# EMG_SS19_Version_2_0.net
KiCad netlist of a schematic drawn in EAGLE
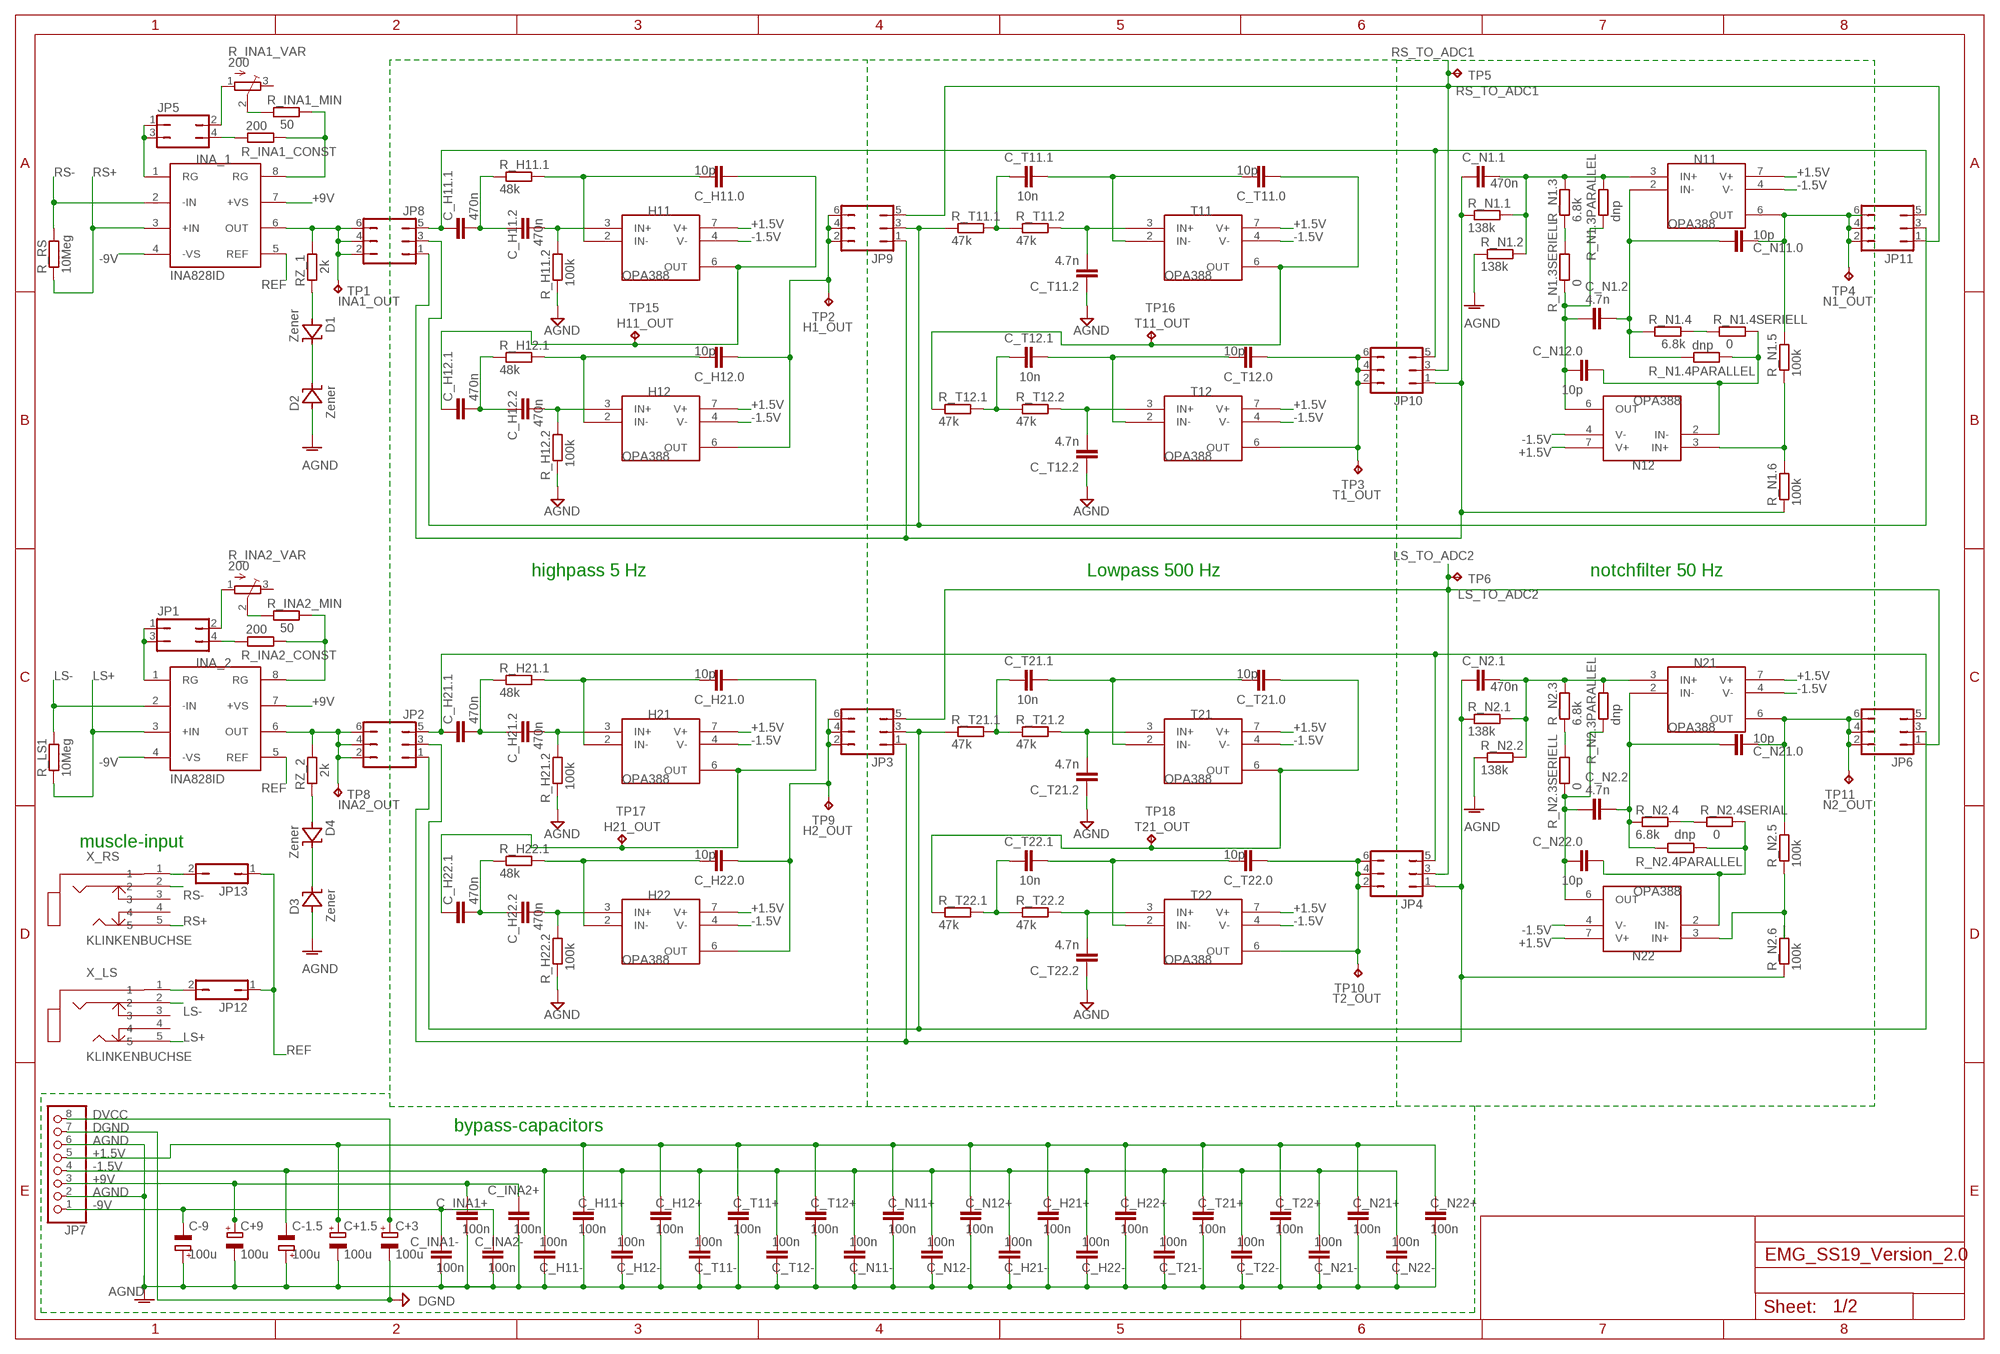
[diagram p0: schematic, sheet 1]
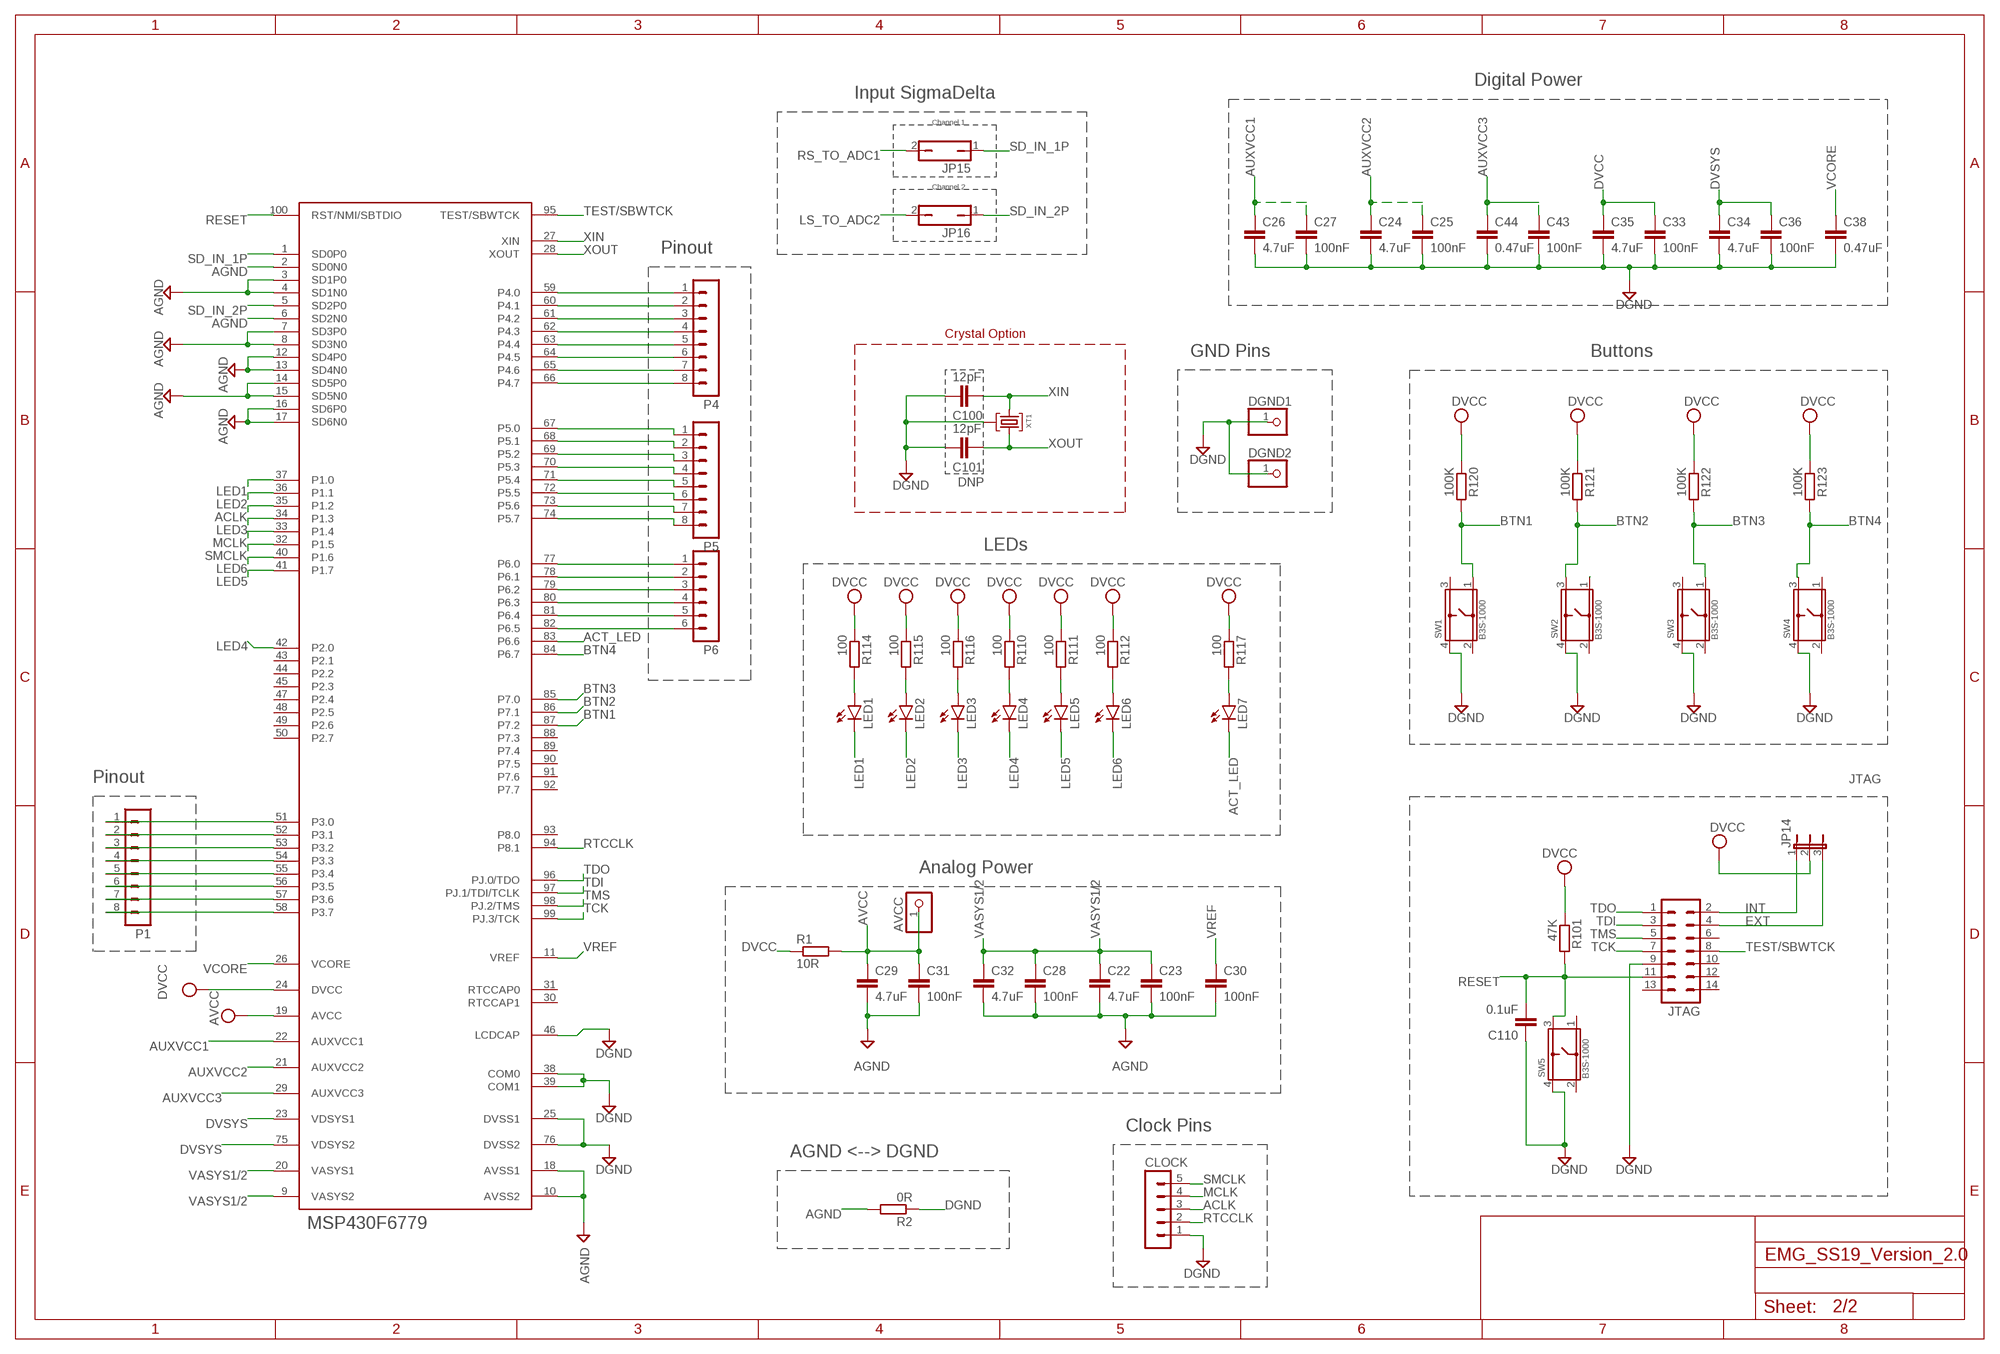
[diagram p1: schematic, sheet 2]

(export (version "E")
  (design (tool "Eeschema 10.0.6"))
  (components
    (comp (ref "AVCC")
      (value "PINHD-1X1")
      (footprint "eagle-import:1X01")
      (libsource (lib "eagle-import") (part "PINHD-1X1"))
    )
    (comp (ref "C22")
      (value "4.7uF")
      (footprint "eagle-import:C0805")
      (libsource (lib "eagle-import") (part "resistor_C-EUC0805"))
    )
    (comp (ref "C23")
      (value "100nF")
      (footprint "eagle-import:C0805")
      (libsource (lib "eagle-import") (part "resistor_C-EUC0805"))
    )
    (comp (ref "C24")
      (value "4.7uF")
      (footprint "eagle-import:C0805")
      (libsource (lib "eagle-import") (part "resistor_C-EUC0805"))
    )
    (comp (ref "C25")
      (value "100nF")
      (footprint "eagle-import:C0805")
      (libsource (lib "eagle-import") (part "resistor_C-EUC0805"))
    )
    (comp (ref "C26")
      (value "4.7uF")
      (footprint "eagle-import:C0805")
      (libsource (lib "eagle-import") (part "resistor_C-EUC0805"))
    )
    (comp (ref "C27")
      (value "100nF")
      (footprint "eagle-import:C0805")
      (libsource (lib "eagle-import") (part "resistor_C-EUC0805"))
    )
    (comp (ref "C28")
      (value "100nF")
      (footprint "eagle-import:C0805")
      (libsource (lib "eagle-import") (part "resistor_C-EUC0805"))
    )
    (comp (ref "C29")
      (value "4.7uF")
      (footprint "eagle-import:C0805")
      (libsource (lib "eagle-import") (part "resistor_C-EUC0805"))
    )
    (comp (ref "C30")
      (value "100nF")
      (footprint "eagle-import:C0805")
      (libsource (lib "eagle-import") (part "resistor_C-EUC0805"))
    )
    (comp (ref "C31")
      (value "100nF")
      (footprint "eagle-import:C0805")
      (libsource (lib "eagle-import") (part "resistor_C-EUC0805"))
    )
    (comp (ref "C32")
      (value "4.7uF")
      (footprint "eagle-import:C0805")
      (libsource (lib "eagle-import") (part "resistor_C-EUC0805"))
    )
    (comp (ref "C33")
      (value "100nF")
      (footprint "eagle-import:C0805")
      (libsource (lib "eagle-import") (part "resistor_C-EUC0805"))
    )
    (comp (ref "C34")
      (value "4.7uF")
      (footprint "eagle-import:C0805")
      (libsource (lib "eagle-import") (part "resistor_C-EUC0805"))
    )
    (comp (ref "C35")
      (value "4.7uF")
      (footprint "eagle-import:C0805")
      (libsource (lib "eagle-import") (part "resistor_C-EUC0805"))
    )
    (comp (ref "C36")
      (value "100nF")
      (footprint "eagle-import:C0805")
      (libsource (lib "eagle-import") (part "resistor_C-EUC0805"))
    )
    (comp (ref "C38")
      (value "0.47uF")
      (footprint "eagle-import:C0805")
      (libsource (lib "eagle-import") (part "resistor_C-EUC0805"))
    )
    (comp (ref "C43")
      (value "100nF")
      (footprint "eagle-import:C0805")
      (libsource (lib "eagle-import") (part "resistor_C-EUC0805"))
    )
    (comp (ref "C44")
      (value "0.47uF")
      (footprint "eagle-import:C0805")
      (libsource (lib "eagle-import") (part "resistor_C-EUC0805"))
    )
    (comp (ref "C100")
      (value "12pF")
      (footprint "eagle-import:C0805")
      (libsource (lib "eagle-import") (part "resistor_C-EUC0805"))
    )
    (comp (ref "C101")
      (value "12pF")
      (footprint "eagle-import:C0805")
      (libsource (lib "eagle-import") (part "resistor_C-EUC0805"))
    )
    (comp (ref "C110")
      (value "0.1uF")
      (footprint "eagle-import:C0805")
      (libsource (lib "eagle-import") (part "resistor_C-EUC0805"))
    )
    (comp (ref "CLOCK")
      (value "MA05-1")
      (footprint "eagle-import:MA05-1")
      (libsource (lib "eagle-import") (part "MA05-1"))
    )
    (comp (ref "DGND1")
      (value "PINHD-1X1")
      (footprint "eagle-import:1X01")
      (libsource (lib "eagle-import") (part "PINHD-1X1"))
    )
    (comp (ref "DGND2")
      (value "PINHD-1X1")
      (footprint "eagle-import:1X01")
      (libsource (lib "eagle-import") (part "PINHD-1X1"))
    )
    (comp (ref "JP14")
      (value "JP2E")
      (footprint "eagle-import:JP2")
      (libsource (lib "eagle-import") (part "JP2E"))
    )
    (comp (ref "JP15")
      (value "JP1Q")
      (footprint "eagle-import:JP1")
      (libsource (lib "eagle-import") (part "JP1Q"))
    )
    (comp (ref "JP16")
      (value "JP1Q")
      (footprint "eagle-import:JP1")
      (libsource (lib "eagle-import") (part "JP1Q"))
    )
    (comp (ref "JTAG")
      (value "ML14")
      (footprint "eagle-import:ML14")
      (libsource (lib "eagle-import") (part "ML14"))
    )
    (comp (ref "LED1")
      (value "LEDCHIP-LED0805")
      (footprint "eagle-import:CHIP-LED0805")
      (libsource (lib "eagle-import") (part "LEDCHIP-LED0805"))
    )
    (comp (ref "LED2")
      (value "LEDCHIP-LED0805")
      (footprint "eagle-import:CHIP-LED0805")
      (libsource (lib "eagle-import") (part "LEDCHIP-LED0805"))
    )
    (comp (ref "LED3")
      (value "LEDCHIP-LED0805")
      (footprint "eagle-import:CHIP-LED0805")
      (libsource (lib "eagle-import") (part "LEDCHIP-LED0805"))
    )
    (comp (ref "LED4")
      (value "LEDCHIP-LED0805")
      (footprint "eagle-import:CHIP-LED0805")
      (libsource (lib "eagle-import") (part "LEDCHIP-LED0805"))
    )
    (comp (ref "LED5")
      (value "LEDCHIP-LED0805")
      (footprint "eagle-import:CHIP-LED0805")
      (libsource (lib "eagle-import") (part "LEDCHIP-LED0805"))
    )
    (comp (ref "LED6")
      (value "LEDCHIP-LED0805")
      (footprint "eagle-import:CHIP-LED0805")
      (libsource (lib "eagle-import") (part "LEDCHIP-LED0805"))
    )
    (comp (ref "LED7")
      (value "LEDCHIP-LED0805")
      (footprint "eagle-import:CHIP-LED0805")
      (libsource (lib "eagle-import") (part "LEDCHIP-LED0805"))
    )
    (comp (ref "P1")
      (value "MA08-1")
      (footprint "eagle-import:MA08-1")
      (libsource (lib "eagle-import") (part "MA08-1"))
    )
    (comp (ref "P4")
      (value "MA08-1")
      (footprint "eagle-import:MA08-1")
      (libsource (lib "eagle-import") (part "MA08-1"))
    )
    (comp (ref "P5")
      (value "MA08-1")
      (footprint "eagle-import:MA08-1")
      (libsource (lib "eagle-import") (part "MA08-1"))
    )
    (comp (ref "P6")
      (value "MA06-1")
      (footprint "eagle-import:MA06-1")
      (libsource (lib "eagle-import") (part "MA06-1"))
    )
    (comp (ref "R1")
      (value "10R")
      (footprint "eagle-import:R0805")
      (libsource (lib "eagle-import") (part "resistor_R-EU_R0805"))
    )
    (comp (ref "R2")
      (value "0R")
      (footprint "eagle-import:R0805")
      (libsource (lib "eagle-import") (part "resistor_R-EU_R0805"))
    )
    (comp (ref "R101")
      (value "47K")
      (footprint "eagle-import:R0805")
      (libsource (lib "eagle-import") (part "resistor_R-EU_R0805"))
    )
    (comp (ref "R110")
      (value "100")
      (footprint "eagle-import:R0805")
      (libsource (lib "eagle-import") (part "resistor_R-EU_R0805"))
    )
    (comp (ref "R111")
      (value "100")
      (footprint "eagle-import:R0805")
      (libsource (lib "eagle-import") (part "resistor_R-EU_R0805"))
    )
    (comp (ref "R112")
      (value "100")
      (footprint "eagle-import:R0805")
      (libsource (lib "eagle-import") (part "resistor_R-EU_R0805"))
    )
    (comp (ref "R114")
      (value "100")
      (footprint "eagle-import:R0805")
      (libsource (lib "eagle-import") (part "resistor_R-EU_R0805"))
    )
    (comp (ref "R115")
      (value "100")
      (footprint "eagle-import:R0805")
      (libsource (lib "eagle-import") (part "resistor_R-EU_R0805"))
    )
    (comp (ref "R116")
      (value "100")
      (footprint "eagle-import:R0805")
      (libsource (lib "eagle-import") (part "resistor_R-EU_R0805"))
    )
    (comp (ref "R117")
      (value "100")
      (footprint "eagle-import:R0805")
      (libsource (lib "eagle-import") (part "resistor_R-EU_R0805"))
    )
    (comp (ref "R120")
      (value "100K")
      (footprint "eagle-import:R0805")
      (libsource (lib "eagle-import") (part "resistor_R-EU_R0805"))
    )
    (comp (ref "R121")
      (value "100K")
      (footprint "eagle-import:R0805")
      (libsource (lib "eagle-import") (part "resistor_R-EU_R0805"))
    )
    (comp (ref "R122")
      (value "100K")
      (footprint "eagle-import:R0805")
      (libsource (lib "eagle-import") (part "resistor_R-EU_R0805"))
    )
    (comp (ref "R123")
      (value "100K")
      (footprint "eagle-import:R0805")
      (libsource (lib "eagle-import") (part "resistor_R-EU_R0805"))
    )
    (comp (ref "SW1")
      (value "B3S-1000")
      (footprint "eagle-import:SW_B3S-1000")
      (fields (field (name "MF") "Omron"))
      (libsource (lib "eagle-import") (part "B3S-1000"))
    )
    (comp (ref "SW2")
      (value "B3S-1000")
      (footprint "eagle-import:SW_B3S-1000")
      (fields (field (name "MF") "Omron"))
      (libsource (lib "eagle-import") (part "B3S-1000"))
    )
    (comp (ref "SW3")
      (value "B3S-1000")
      (footprint "eagle-import:SW_B3S-1000")
      (fields (field (name "MF") "Omron"))
      (libsource (lib "eagle-import") (part "B3S-1000"))
    )
    (comp (ref "SW4")
      (value "B3S-1000")
      (footprint "eagle-import:SW_B3S-1000")
      (fields (field (name "MF") "Omron"))
      (libsource (lib "eagle-import") (part "B3S-1000"))
    )
    (comp (ref "SW5")
      (value "B3S-1000")
      (footprint "eagle-import:SW_B3S-1000")
      (fields (field (name "MF") "Omron"))
      (libsource (lib "eagle-import") (part "B3S-1000"))
    )
    (comp (ref "U$1")
      (value "MSP430F6779PZ")
      (footprint "eagle-import:S-PQFP-G100(PZ)")
      (libsource (lib "eagle-import") (part "MSP430F6779PZ"))
    )
    (comp (ref "XT1")
      (value "CM200T")
      (footprint "eagle-import:CM200T")
      (libsource (lib "eagle-import") (part "CM200T"))
    )
    (comp (ref "C+1.5")
      (value "100u")
      (footprint "eagle-import:RADIAL_SMD_ELKO_6_3")
      (fields (field (name "MF") "Wurth Electronics") (field (name "MP") "865080545012"))
      (libsource (lib "eagle-import") (part "ELKO_SMD"))
    )
    (comp (ref "C+3")
      (value "100u")
      (footprint "eagle-import:RADIAL_SMD_ELKO_6_3")
      (fields (field (name "MF") "Wurth Electronics") (field (name "MP") "865080545012"))
      (libsource (lib "eagle-import") (part "ELKO_SMD"))
    )
    (comp (ref "C+9")
      (value "100u")
      (footprint "eagle-import:RADIAL_SMD_ELKO_6_3")
      (fields (field (name "MF") "Wurth Electronics") (field (name "MP") "865080545012"))
      (libsource (lib "eagle-import") (part "ELKO_SMD"))
    )
    (comp (ref "C-1.5")
      (value "100u")
      (footprint "eagle-import:RADIAL_SMD_ELKO_6_3")
      (fields (field (name "MF") "Wurth Electronics") (field (name "MP") "865080545012"))
      (libsource (lib "eagle-import") (part "ELKO_SMD"))
    )
    (comp (ref "C-9")
      (value "100u")
      (footprint "eagle-import:RADIAL_SMD_ELKO_6_3")
      (fields (field (name "MF") "Wurth Electronics") (field (name "MP") "865080545012"))
      (libsource (lib "eagle-import") (part "ELKO_SMD"))
    )
    (comp (ref "C_H11+")
      (value "100n")
      (footprint "eagle-import:C0805")
      (libsource (lib "eagle-import") (part "C-EUC0805"))
    )
    (comp (ref "C_H11-")
      (value "100n")
      (footprint "eagle-import:C0805")
      (libsource (lib "eagle-import") (part "C-EUC0805"))
    )
    (comp (ref "C_H11.0")
      (value "10p")
      (footprint "eagle-import:C0805")
      (libsource (lib "eagle-import") (part "C-EUC0805"))
    )
    (comp (ref "C_H11.1")
      (value "470n")
      (footprint "eagle-import:C0805")
      (libsource (lib "eagle-import") (part "C-EUC0805"))
    )
    (comp (ref "C_H11.2")
      (value "470n")
      (footprint "eagle-import:C0805")
      (libsource (lib "eagle-import") (part "C-EUC0805"))
    )
    (comp (ref "C_H12+")
      (value "100n")
      (footprint "eagle-import:C0805")
      (libsource (lib "eagle-import") (part "C-EUC0805"))
    )
    (comp (ref "C_H12-")
      (value "100n")
      (footprint "eagle-import:C0805")
      (libsource (lib "eagle-import") (part "C-EUC0805"))
    )
    (comp (ref "C_H12.0")
      (value "10p")
      (footprint "eagle-import:C0805")
      (libsource (lib "eagle-import") (part "C-EUC0805"))
    )
    (comp (ref "C_H12.1")
      (value "470n")
      (footprint "eagle-import:C0805")
      (libsource (lib "eagle-import") (part "C-EUC0805"))
    )
    (comp (ref "C_H12.2")
      (value "470n")
      (footprint "eagle-import:C0805")
      (libsource (lib "eagle-import") (part "C-EUC0805"))
    )
    (comp (ref "C_H21+")
      (value "100n")
      (footprint "eagle-import:C0805")
      (libsource (lib "eagle-import") (part "C-EUC0805"))
    )
    (comp (ref "C_H21-")
      (value "100n")
      (footprint "eagle-import:C0805")
      (libsource (lib "eagle-import") (part "C-EUC0805"))
    )
    (comp (ref "C_H21.0")
      (value "10p")
      (footprint "eagle-import:C0805")
      (libsource (lib "eagle-import") (part "C-EUC0805"))
    )
    (comp (ref "C_H21.1")
      (value "470n")
      (footprint "eagle-import:C0805")
      (libsource (lib "eagle-import") (part "C-EUC0805"))
    )
    (comp (ref "C_H21.2")
      (value "470n")
      (footprint "eagle-import:C0805")
      (libsource (lib "eagle-import") (part "C-EUC0805"))
    )
    (comp (ref "C_H22+")
      (value "100n")
      (footprint "eagle-import:C0805")
      (libsource (lib "eagle-import") (part "C-EUC0805"))
    )
    (comp (ref "C_H22-")
      (value "100n")
      (footprint "eagle-import:C0805")
      (libsource (lib "eagle-import") (part "C-EUC0805"))
    )
    (comp (ref "C_H22.0")
      (value "10p")
      (footprint "eagle-import:C0805")
      (libsource (lib "eagle-import") (part "C-EUC0805"))
    )
    (comp (ref "C_H22.1")
      (value "470n")
      (footprint "eagle-import:C0805")
      (libsource (lib "eagle-import") (part "C-EUC0805"))
    )
    (comp (ref "C_H22.2")
      (value "470n")
      (footprint "eagle-import:C0805")
      (libsource (lib "eagle-import") (part "C-EUC0805"))
    )
    (comp (ref "C_INA1+")
      (value "100n")
      (footprint "eagle-import:C0805")
      (libsource (lib "eagle-import") (part "C-EUC0805"))
    )
    (comp (ref "C_INA1-")
      (value "100n")
      (footprint "eagle-import:C0805")
      (libsource (lib "eagle-import") (part "C-EUC0805"))
    )
    (comp (ref "C_INA2+")
      (value "100n")
      (footprint "eagle-import:C0805")
      (libsource (lib "eagle-import") (part "C-EUC0805"))
    )
    (comp (ref "C_INA2-")
      (value "100n")
      (footprint "eagle-import:C0805")
      (libsource (lib "eagle-import") (part "C-EUC0805"))
    )
    (comp (ref "C_N1.1")
      (value "470n")
      (footprint "eagle-import:C0805")
      (libsource (lib "eagle-import") (part "C-EUC0805"))
    )
    (comp (ref "C_N1.2")
      (value "4.7n")
      (footprint "eagle-import:C0805")
      (libsource (lib "eagle-import") (part "C-EUC0805"))
    )
    (comp (ref "C_N2.1")
      (value "470n")
      (footprint "eagle-import:C0805")
      (libsource (lib "eagle-import") (part "C-EUC0805"))
    )
    (comp (ref "C_N2.2")
      (value "4.7n")
      (footprint "eagle-import:C0805")
      (libsource (lib "eagle-import") (part "C-EUC0805"))
    )
    (comp (ref "C_N11+")
      (value "100n")
      (footprint "eagle-import:C0805")
      (libsource (lib "eagle-import") (part "C-EUC0805"))
    )
    (comp (ref "C_N11-")
      (value "100n")
      (footprint "eagle-import:C0805")
      (libsource (lib "eagle-import") (part "C-EUC0805"))
    )
    (comp (ref "C_N11.0")
      (value "10p")
      (footprint "eagle-import:C0805")
      (libsource (lib "eagle-import") (part "C-EUC0805"))
    )
    (comp (ref "C_N12+")
      (value "100n")
      (footprint "eagle-import:C0805")
      (libsource (lib "eagle-import") (part "C-EUC0805"))
    )
    (comp (ref "C_N12-")
      (value "100n")
      (footprint "eagle-import:C0805")
      (libsource (lib "eagle-import") (part "C-EUC0805"))
    )
    (comp (ref "C_N12.0")
      (value "10p")
      (footprint "eagle-import:C0805")
      (libsource (lib "eagle-import") (part "C-EUC0805"))
    )
    (comp (ref "C_N21+")
      (value "100n")
      (footprint "eagle-import:C0805")
      (libsource (lib "eagle-import") (part "C-EUC0805"))
    )
    (comp (ref "C_N21-")
      (value "100n")
      (footprint "eagle-import:C0805")
      (libsource (lib "eagle-import") (part "C-EUC0805"))
    )
    (comp (ref "C_N21.0")
      (value "10p")
      (footprint "eagle-import:C0805")
      (libsource (lib "eagle-import") (part "C-EUC0805"))
    )
    (comp (ref "C_N22+")
      (value "100n")
      (footprint "eagle-import:C0805")
      (libsource (lib "eagle-import") (part "C-EUC0805"))
    )
    (comp (ref "C_N22-")
      (value "100n")
      (footprint "eagle-import:C0805")
      (libsource (lib "eagle-import") (part "C-EUC0805"))
    )
    (comp (ref "C_N22.0")
      (value "10p")
      (footprint "eagle-import:C0805")
      (libsource (lib "eagle-import") (part "C-EUC0805"))
    )
    (comp (ref "C_T11+")
      (value "100n")
      (footprint "eagle-import:C0805")
      (libsource (lib "eagle-import") (part "C-EUC0805"))
    )
    (comp (ref "C_T11-")
      (value "100n")
      (footprint "eagle-import:C0805")
      (libsource (lib "eagle-import") (part "C-EUC0805"))
    )
    (comp (ref "C_T11.0")
      (value "10p")
      (footprint "eagle-import:C0805")
      (libsource (lib "eagle-import") (part "C-EUC0805"))
    )
    (comp (ref "C_T11.1")
      (value "10n")
      (footprint "eagle-import:C0805")
      (libsource (lib "eagle-import") (part "C-EUC0805"))
    )
    (comp (ref "C_T11.2")
      (value "4.7n")
      (footprint "eagle-import:C0805")
      (libsource (lib "eagle-import") (part "C-EUC0805"))
    )
    (comp (ref "C_T12+")
      (value "100n")
      (footprint "eagle-import:C0805")
      (libsource (lib "eagle-import") (part "C-EUC0805"))
    )
    (comp (ref "C_T12-")
      (value "100n")
      (footprint "eagle-import:C0805")
      (libsource (lib "eagle-import") (part "C-EUC0805"))
    )
    (comp (ref "C_T12.0")
      (value "10p")
      (footprint "eagle-import:C0805")
      (libsource (lib "eagle-import") (part "C-EUC0805"))
    )
    (comp (ref "C_T12.1")
      (value "10n")
      (footprint "eagle-import:C0805")
      (libsource (lib "eagle-import") (part "C-EUC0805"))
    )
    (comp (ref "C_T12.2")
      (value "4.7n")
      (footprint "eagle-import:C0805")
      (libsource (lib "eagle-import") (part "C-EUC0805"))
    )
    (comp (ref "C_T21+")
      (value "100n")
      (footprint "eagle-import:C0805")
      (libsource (lib "eagle-import") (part "C-EUC0805"))
    )
    (comp (ref "C_T21-")
      (value "100n")
      (footprint "eagle-import:C0805")
      (libsource (lib "eagle-import") (part "C-EUC0805"))
    )
    (comp (ref "C_T21.0")
      (value "10p")
      (footprint "eagle-import:C0805")
      (libsource (lib "eagle-import") (part "C-EUC0805"))
    )
    (comp (ref "C_T21.1")
      (value "10n")
      (footprint "eagle-import:C0805")
      (libsource (lib "eagle-import") (part "C-EUC0805"))
    )
    (comp (ref "C_T21.2")
      (value "4.7n")
      (footprint "eagle-import:C0805")
      (libsource (lib "eagle-import") (part "C-EUC0805"))
    )
    (comp (ref "C_T22+")
      (value "100n")
      (footprint "eagle-import:C0805")
      (libsource (lib "eagle-import") (part "C-EUC0805"))
    )
    (comp (ref "C_T22-")
      (value "100n")
      (footprint "eagle-import:C0805")
      (libsource (lib "eagle-import") (part "C-EUC0805"))
    )
    (comp (ref "C_T22.0")
      (value "10p")
      (footprint "eagle-import:C0805")
      (libsource (lib "eagle-import") (part "C-EUC0805"))
    )
    (comp (ref "C_T22.1")
      (value "10n")
      (footprint "eagle-import:C0805")
      (libsource (lib "eagle-import") (part "C-EUC0805"))
    )
    (comp (ref "C_T22.2")
      (value "4.7n")
      (footprint "eagle-import:C0805")
      (libsource (lib "eagle-import") (part "C-EUC0805"))
    )
    (comp (ref "D1")
      (value "Zener")
      (footprint "eagle-import:SOT-23")
      (fields (field (name "MF") "Diodes Inc.") (field (name "MP") "ZXCT1109SA-7"))
      (libsource (lib "eagle-import") (part "ZENER_SMD_ZD_8.2"))
    )
    (comp (ref "D2")
      (value "Zener")
      (footprint "eagle-import:SOT-23")
      (fields (field (name "MF") "Diodes Inc.") (field (name "MP") "ZXCT1109SA-7"))
      (libsource (lib "eagle-import") (part "ZENER_SMD_ZD_8.2"))
    )
    (comp (ref "D3")
      (value "Zener")
      (footprint "eagle-import:SOT-23")
      (fields (field (name "MF") "Diodes Inc.") (field (name "MP") "ZXCT1109SA-7"))
      (libsource (lib "eagle-import") (part "ZENER_SMD_ZD_8.2"))
    )
    (comp (ref "D4")
      (value "Zener")
      (footprint "eagle-import:SOT-23")
      (fields (field (name "MF") "Diodes Inc.") (field (name "MP") "ZXCT1109SA-7"))
      (libsource (lib "eagle-import") (part "ZENER_SMD_ZD_8.2"))
    )
    (comp (ref "H11")
      (value "OPA388")
      (footprint "eagle-import:SOIC127P600X175-8N")
      (libsource (lib "eagle-import") (part "OPA388"))
    )
    (comp (ref "H12")
      (value "OPA388")
      (footprint "eagle-import:SOIC127P600X175-8N")
      (libsource (lib "eagle-import") (part "OPA388"))
    )
    (comp (ref "H21")
      (value "OPA388")
      (footprint "eagle-import:SOIC127P600X175-8N")
      (libsource (lib "eagle-import") (part "OPA388"))
    )
    (comp (ref "H22")
      (value "OPA388")
      (footprint "eagle-import:SOIC127P600X175-8N")
      (libsource (lib "eagle-import") (part "OPA388"))
    )
    (comp (ref "INA_1")
      (value "INA828ID")
      (footprint "eagle-import:SOIC8")
      (fields (field (name "DIGI-KEY_PART_NUMBER") "296-47415-ND") (field (name "MF") "Texas Instruments"))
      (libsource (lib "eagle-import") (part "INA828ID"))
    )
    (comp (ref "INA_2")
      (value "INA828ID")
      (footprint "eagle-import:SOIC8")
      (fields (field (name "DIGI-KEY_PART_NUMBER") "296-47415-ND") (field (name "MF") "Texas Instruments"))
      (libsource (lib "eagle-import") (part "INA828ID"))
    )
    (comp (ref "JP1")
      (value "JP2Q")
      (footprint "eagle-import:JP2Q")
      (libsource (lib "eagle-import") (part "JP2Q"))
    )
    (comp (ref "JP2")
      (value "JP3Q")
      (footprint "eagle-import:JP3Q")
      (libsource (lib "eagle-import") (part "JP3Q"))
    )
    (comp (ref "JP3")
      (value "JP3Q")
      (footprint "eagle-import:JP3Q")
      (libsource (lib "eagle-import") (part "JP3Q"))
    )
    (comp (ref "JP4")
      (value "JP3Q")
      (footprint "eagle-import:JP3Q")
      (libsource (lib "eagle-import") (part "JP3Q"))
    )
    (comp (ref "JP5")
      (value "JP2Q")
      (footprint "eagle-import:JP2Q")
      (libsource (lib "eagle-import") (part "JP2Q"))
    )
    (comp (ref "JP6")
      (value "JP3Q")
      (footprint "eagle-import:JP3Q")
      (libsource (lib "eagle-import") (part "JP3Q"))
    )
    (comp (ref "JP7")
      (value "PINHD-1X8")
      (footprint "eagle-import:1X08")
      (libsource (lib "eagle-import") (part "PINHD-1X8"))
    )
    (comp (ref "JP8")
      (value "JP3Q")
      (footprint "eagle-import:JP3Q")
      (libsource (lib "eagle-import") (part "JP3Q"))
    )
    (comp (ref "JP9")
      (value "JP3Q")
      (footprint "eagle-import:JP3Q")
      (libsource (lib "eagle-import") (part "JP3Q"))
    )
    (comp (ref "JP10")
      (value "JP3Q")
      (footprint "eagle-import:JP3Q")
      (libsource (lib "eagle-import") (part "JP3Q"))
    )
    (comp (ref "JP11")
      (value "JP3Q")
      (footprint "eagle-import:JP3Q")
      (libsource (lib "eagle-import") (part "JP3Q"))
    )
    (comp (ref "JP12")
      (value "JP1Q")
      (footprint "eagle-import:JP1")
      (libsource (lib "eagle-import") (part "JP1Q"))
    )
    (comp (ref "JP13")
      (value "JP1Q")
      (footprint "eagle-import:JP1")
      (libsource (lib "eagle-import") (part "JP1Q"))
    )
    (comp (ref "N11")
      (value "OPA388")
      (footprint "eagle-import:SOIC127P600X175-8N")
      (libsource (lib "eagle-import") (part "OPA388"))
    )
    (comp (ref "N12")
      (value "OPA388")
      (footprint "eagle-import:SOIC127P600X175-8N")
      (libsource (lib "eagle-import") (part "OPA388"))
    )
    (comp (ref "N21")
      (value "OPA388")
      (footprint "eagle-import:SOIC127P600X175-8N")
      (libsource (lib "eagle-import") (part "OPA388"))
    )
    (comp (ref "N22")
      (value "OPA388")
      (footprint "eagle-import:SOIC127P600X175-8N")
      (libsource (lib "eagle-import") (part "OPA388"))
    )
    (comp (ref "RZ_1")
      (value "2k")
      (footprint "eagle-import:R0805")
      (libsource (lib "eagle-import") (part "R-EU_R0805"))
    )
    (comp (ref "RZ_2")
      (value "2k")
      (footprint "eagle-import:R0805")
      (libsource (lib "eagle-import") (part "R-EU_R0805"))
    )
    (comp (ref "R_H11.1")
      (value "48k")
      (footprint "eagle-import:R0805")
      (libsource (lib "eagle-import") (part "R-EU_R0805"))
    )
    (comp (ref "R_H11.2")
      (value "100k")
      (footprint "eagle-import:R0805")
      (libsource (lib "eagle-import") (part "R-EU_R0805"))
    )
    (comp (ref "R_H12.1")
      (value "48k")
      (footprint "eagle-import:R0805")
      (libsource (lib "eagle-import") (part "R-EU_R0805"))
    )
    (comp (ref "R_H12.2")
      (value "100k")
      (footprint "eagle-import:R0805")
      (libsource (lib "eagle-import") (part "R-EU_R0805"))
    )
    (comp (ref "R_H21.1")
      (value "48k")
      (footprint "eagle-import:R0805")
      (libsource (lib "eagle-import") (part "R-EU_R0805"))
    )
    (comp (ref "R_H21.2")
      (value "100k")
      (footprint "eagle-import:R0805")
      (libsource (lib "eagle-import") (part "R-EU_R0805"))
    )
    (comp (ref "R_H22.1")
      (value "48k")
      (footprint "eagle-import:R0805")
      (libsource (lib "eagle-import") (part "R-EU_R0805"))
    )
    (comp (ref "R_H22.2")
      (value "100k")
      (footprint "eagle-import:R0805")
      (libsource (lib "eagle-import") (part "R-EU_R0805"))
    )
    (comp (ref "R_INA1_CONST")
      (value "200")
      (footprint "eagle-import:R0805")
      (libsource (lib "eagle-import") (part "R-EU_R0805"))
    )
    (comp (ref "R_INA1_MIN")
      (value "50")
      (footprint "eagle-import:R0805")
      (libsource (lib "eagle-import") (part "R-EU_R0805"))
    )
    (comp (ref "R_INA1_VAR")
      (value "200")
      (footprint "eagle-import:SM-42_43W")
      (fields (field (name "SPICEPREFIX") "J"))
      (libsource (lib "eagle-import") (part "TRIM_EU-SM-42/43W"))
    )
    (comp (ref "R_INA2_CONST")
      (value "200")
      (footprint "eagle-import:R0805")
      (libsource (lib "eagle-import") (part "R-EU_R0805"))
    )
    (comp (ref "R_INA2_MIN")
      (value "50")
      (footprint "eagle-import:R0805")
      (libsource (lib "eagle-import") (part "R-EU_R0805"))
    )
    (comp (ref "R_INA2_VAR")
      (value "200")
      (footprint "eagle-import:SM-42_43W")
      (fields (field (name "SPICEPREFIX") "J"))
      (libsource (lib "eagle-import") (part "TRIM_EU-SM-42/43W"))
    )
    (comp (ref "R_LS1")
      (value "10Meg")
      (footprint "eagle-import:R0805")
      (libsource (lib "eagle-import") (part "R-EU_R0805"))
    )
    (comp (ref "R_N1.1")
      (value "138k")
      (footprint "eagle-import:R0805")
      (libsource (lib "eagle-import") (part "R-EU_R0805"))
    )
    (comp (ref "R_N1.2")
      (value "138k")
      (footprint "eagle-import:R0805")
      (libsource (lib "eagle-import") (part "R-EU_R0805"))
    )
    (comp (ref "R_N1.3")
      (value "6.8k")
      (footprint "eagle-import:R0805")
      (libsource (lib "eagle-import") (part "R-EU_R0805"))
    )
    (comp (ref "R_N1.3PARALLEL")
      (value "dnp")
      (footprint "eagle-import:R0805")
      (libsource (lib "eagle-import") (part "R-EU_R0805"))
    )
    (comp (ref "R_N1.3SERIELL")
      (value "0")
      (footprint "eagle-import:R0805")
      (libsource (lib "eagle-import") (part "R-EU_R0805"))
    )
    (comp (ref "R_N1.4")
      (value "6.8k")
      (footprint "eagle-import:R0805")
      (libsource (lib "eagle-import") (part "R-EU_R0805"))
    )
    (comp (ref "R_N1.4PARALLEL")
      (value "dnp")
      (footprint "eagle-import:R0805")
      (libsource (lib "eagle-import") (part "R-EU_R0805"))
    )
    (comp (ref "R_N1.4SERIELL")
      (value "0")
      (footprint "eagle-import:R0805")
      (libsource (lib "eagle-import") (part "R-EU_R0805"))
    )
    (comp (ref "R_N1.5")
      (value "100k")
      (footprint "eagle-import:R0805")
      (libsource (lib "eagle-import") (part "R-EU_R0805"))
    )
    (comp (ref "R_N1.6")
      (value "100k")
      (footprint "eagle-import:R0805")
      (libsource (lib "eagle-import") (part "R-EU_R0805"))
    )
    (comp (ref "R_N2.1")
      (value "138k")
      (footprint "eagle-import:R0805")
      (libsource (lib "eagle-import") (part "R-EU_R0805"))
    )
    (comp (ref "R_N2.2")
      (value "138k")
      (footprint "eagle-import:R0805")
      (libsource (lib "eagle-import") (part "R-EU_R0805"))
    )
    (comp (ref "R_N2.3")
      (value "6.8k")
      (footprint "eagle-import:R0805")
      (libsource (lib "eagle-import") (part "R-EU_R0805"))
    )
    (comp (ref "R_N2.3PARALLEL")
      (value "dnp")
      (footprint "eagle-import:R0805")
      (libsource (lib "eagle-import") (part "R-EU_R0805"))
    )
    (comp (ref "R_N2.3SERIELL")
      (value "0")
      (footprint "eagle-import:R0805")
      (libsource (lib "eagle-import") (part "R-EU_R0805"))
    )
    (comp (ref "R_N2.4")
      (value "6.8k")
      (footprint "eagle-import:R0805")
      (libsource (lib "eagle-import") (part "R-EU_R0805"))
    )
    (comp (ref "R_N2.4PARALLEL")
      (value "dnp")
      (footprint "eagle-import:R0805")
      (libsource (lib "eagle-import") (part "R-EU_R0805"))
    )
    (comp (ref "R_N2.4SERIAL")
      (value "0")
      (footprint "eagle-import:R0805")
      (libsource (lib "eagle-import") (part "R-EU_R0805"))
    )
    (comp (ref "R_N2.5")
      (value "100k")
      (footprint "eagle-import:R0805")
      (libsource (lib "eagle-import") (part "R-EU_R0805"))
    )
    (comp (ref "R_N2.6")
      (value "100k")
      (footprint "eagle-import:R0805")
      (libsource (lib "eagle-import") (part "R-EU_R0805"))
    )
    (comp (ref "R_RS")
      (value "10Meg")
      (footprint "eagle-import:R0805")
      (libsource (lib "eagle-import") (part "R-EU_R0805"))
    )
    (comp (ref "R_T11.1")
      (value "47k")
      (footprint "eagle-import:R0805")
      (libsource (lib "eagle-import") (part "R-EU_R0805"))
    )
    (comp (ref "R_T11.2")
      (value "47k")
      (footprint "eagle-import:R0805")
      (libsource (lib "eagle-import") (part "R-EU_R0805"))
    )
    (comp (ref "R_T12.1")
      (value "47k")
      (footprint "eagle-import:R0805")
      (libsource (lib "eagle-import") (part "R-EU_R0805"))
    )
    (comp (ref "R_T12.2")
      (value "47k")
      (footprint "eagle-import:R0805")
      (libsource (lib "eagle-import") (part "R-EU_R0805"))
    )
    (comp (ref "R_T21.1")
      (value "47k")
      (footprint "eagle-import:R0805")
      (libsource (lib "eagle-import") (part "R-EU_R0805"))
    )
    (comp (ref "R_T21.2")
      (value "47k")
      (footprint "eagle-import:R0805")
      (libsource (lib "eagle-import") (part "R-EU_R0805"))
    )
    (comp (ref "R_T22.1")
      (value "47k")
      (footprint "eagle-import:R0805")
      (libsource (lib "eagle-import") (part "R-EU_R0805"))
    )
    (comp (ref "R_T22.2")
      (value "47k")
      (footprint "eagle-import:R0805")
      (libsource (lib "eagle-import") (part "R-EU_R0805"))
    )
    (comp (ref "T11")
      (value "OPA388")
      (footprint "eagle-import:SOIC127P600X175-8N")
      (libsource (lib "eagle-import") (part "OPA388"))
    )
    (comp (ref "T12")
      (value "OPA388")
      (footprint "eagle-import:SOIC127P600X175-8N")
      (libsource (lib "eagle-import") (part "OPA388"))
    )
    (comp (ref "T21")
      (value "OPA388")
      (footprint "eagle-import:SOIC127P600X175-8N")
      (libsource (lib "eagle-import") (part "OPA388"))
    )
    (comp (ref "T22")
      (value "OPA388")
      (footprint "eagle-import:SOIC127P600X175-8N")
      (libsource (lib "eagle-import") (part "OPA388"))
    )
    (comp (ref "TP1")
      (value "TPPAD1-13")
      (footprint "eagle-import:P1-13")
      (libsource (lib "eagle-import") (part "TPPAD1-13"))
    )
    (comp (ref "TP2")
      (value "TPPAD1-13")
      (footprint "eagle-import:P1-13")
      (libsource (lib "eagle-import") (part "TPPAD1-13"))
    )
    (comp (ref "TP3")
      (value "TPPAD1-13")
      (footprint "eagle-import:P1-13")
      (libsource (lib "eagle-import") (part "TPPAD1-13"))
    )
    (comp (ref "TP4")
      (value "TPPAD1-13")
      (footprint "eagle-import:P1-13")
      (libsource (lib "eagle-import") (part "TPPAD1-13"))
    )
    (comp (ref "TP5")
      (value "RS_TO_ADC")
      (footprint "eagle-import:P1-13")
      (libsource (lib "eagle-import") (part "TPPAD1-13"))
    )
    (comp (ref "TP6")
      (value "LS_TO_ADC")
      (footprint "eagle-import:P1-13")
      (libsource (lib "eagle-import") (part "TPPAD1-13"))
    )
    (comp (ref "TP8")
      (value "TPPAD1-13")
      (footprint "eagle-import:P1-13")
      (libsource (lib "eagle-import") (part "TPPAD1-13"))
    )
    (comp (ref "TP9")
      (value "TPPAD1-13")
      (footprint "eagle-import:P1-13")
      (libsource (lib "eagle-import") (part "TPPAD1-13"))
    )
    (comp (ref "TP10")
      (value "TPPAD1-13")
      (footprint "eagle-import:P1-13")
      (libsource (lib "eagle-import") (part "TPPAD1-13"))
    )
    (comp (ref "TP11")
      (value "TPPAD1-13")
      (footprint "eagle-import:P1-13")
      (libsource (lib "eagle-import") (part "TPPAD1-13"))
    )
    (comp (ref "TP15")
      (value "TPPAD1-13")
      (footprint "eagle-import:P1-13")
      (libsource (lib "eagle-import") (part "TPPAD1-13"))
    )
    (comp (ref "TP16")
      (value "TPPAD1-13")
      (footprint "eagle-import:P1-13")
      (libsource (lib "eagle-import") (part "TPPAD1-13"))
    )
    (comp (ref "TP17")
      (value "TPPAD1-13")
      (footprint "eagle-import:P1-13")
      (libsource (lib "eagle-import") (part "TPPAD1-13"))
    )
    (comp (ref "TP18")
      (value "TPPAD1-13")
      (footprint "eagle-import:P1-13")
      (libsource (lib "eagle-import") (part "TPPAD1-13"))
    )
    (comp (ref "X_LS")
      (value "KLINKENBUCHSE")
      (footprint "eagle-import:FC68131-5P")
      (fields (field (name "MF") "Cliff") (field (name "MP") "FC68131"))
      (libsource (lib "eagle-import") (part "KLINKENBUCHSE"))
    )
    (comp (ref "X_RS")
      (value "KLINKENBUCHSE")
      (footprint "eagle-import:FC68131-5P")
      (fields (field (name "MF") "Cliff") (field (name "MP") "FC68131"))
      (libsource (lib "eagle-import") (part "KLINKENBUCHSE"))
    )
  )
  (nets
    (net (code "1") (name "+1.5V") (class "Default")
      (node (ref "C+1.5") (pin "+") (pinfunction "+_+") (pintype "passive"))
      (node (ref "C_H11+") (pin "1") (pinfunction "1_1") (pintype "passive"))
      (node (ref "C_H12+") (pin "1") (pinfunction "1_1") (pintype "passive"))
      (node (ref "C_H21+") (pin "1") (pinfunction "1_1") (pintype "passive"))
      (node (ref "C_H22+") (pin "1") (pinfunction "1_1") (pintype "passive"))
      (node (ref "C_N11+") (pin "1") (pinfunction "1_1") (pintype "passive"))
      (node (ref "C_N12+") (pin "1") (pinfunction "1_1") (pintype "passive"))
      (node (ref "C_N21+") (pin "1") (pinfunction "1_1") (pintype "passive"))
      (node (ref "C_N22+") (pin "1") (pinfunction "1_1") (pintype "passive"))
      (node (ref "C_T11+") (pin "1") (pinfunction "1_1") (pintype "passive"))
      (node (ref "C_T12+") (pin "1") (pinfunction "1_1") (pintype "passive"))
      (node (ref "C_T21+") (pin "1") (pinfunction "1_1") (pintype "passive"))
      (node (ref "C_T22+") (pin "1") (pinfunction "1_1") (pintype "passive"))
      (node (ref "H11") (pin "7") (pinfunction "V+_7") (pintype "power_in"))
      (node (ref "H12") (pin "7") (pinfunction "V+_7") (pintype "power_in"))
      (node (ref "H21") (pin "7") (pinfunction "V+_7") (pintype "power_in"))
      (node (ref "H22") (pin "7") (pinfunction "V+_7") (pintype "power_in"))
      (node (ref "JP7") (pin "5") (pinfunction "5_5") (pintype "passive"))
      (node (ref "N11") (pin "7") (pinfunction "V+_7") (pintype "power_in"))
      (node (ref "N12") (pin "7") (pinfunction "V+_7") (pintype "power_in"))
      (node (ref "N21") (pin "7") (pinfunction "V+_7") (pintype "power_in"))
      (node (ref "N22") (pin "7") (pinfunction "V+_7") (pintype "power_in"))
      (node (ref "T11") (pin "7") (pinfunction "V+_7") (pintype "power_in"))
      (node (ref "T12") (pin "7") (pinfunction "V+_7") (pintype "power_in"))
      (node (ref "T21") (pin "7") (pinfunction "V+_7") (pintype "power_in"))
      (node (ref "T22") (pin "7") (pinfunction "V+_7") (pintype "power_in"))
    )
    (net (code "2") (name "+9V") (class "Default")
      (node (ref "C+9") (pin "+") (pinfunction "+_+") (pintype "passive"))
      (node (ref "C_INA1+") (pin "1") (pinfunction "1_1") (pintype "passive"))
      (node (ref "C_INA2+") (pin "1") (pinfunction "1_1") (pintype "passive"))
      (node (ref "INA_1") (pin "7") (pinfunction "+VS_7") (pintype "bidirectional"))
      (node (ref "INA_2") (pin "7") (pinfunction "+VS_7") (pintype "bidirectional"))
      (node (ref "JP7") (pin "3") (pinfunction "3_3") (pintype "passive"))
    )
    (net (code "3") (name "-1.5V") (class "Default")
      (node (ref "C-1.5") (pin "-") (pinfunction "-_-") (pintype "passive"))
      (node (ref "C_H11-") (pin "2") (pinfunction "2_2") (pintype "passive"))
      (node (ref "C_H12-") (pin "2") (pinfunction "2_2") (pintype "passive"))
      (node (ref "C_H21-") (pin "2") (pinfunction "2_2") (pintype "passive"))
      (node (ref "C_H22-") (pin "2") (pinfunction "2_2") (pintype "passive"))
      (node (ref "C_N11-") (pin "2") (pinfunction "2_2") (pintype "passive"))
      (node (ref "C_N12-") (pin "2") (pinfunction "2_2") (pintype "passive"))
      (node (ref "C_N21-") (pin "2") (pinfunction "2_2") (pintype "passive"))
      (node (ref "C_N22-") (pin "2") (pinfunction "2_2") (pintype "passive"))
      (node (ref "C_T11-") (pin "2") (pinfunction "2_2") (pintype "passive"))
      (node (ref "C_T12-") (pin "2") (pinfunction "2_2") (pintype "passive"))
      (node (ref "C_T21-") (pin "2") (pinfunction "2_2") (pintype "passive"))
      (node (ref "C_T22-") (pin "2") (pinfunction "2_2") (pintype "passive"))
      (node (ref "H11") (pin "4") (pinfunction "V-_4") (pintype "power_in"))
      (node (ref "H12") (pin "4") (pinfunction "V-_4") (pintype "power_in"))
      (node (ref "H21") (pin "4") (pinfunction "V-_4") (pintype "power_in"))
      (node (ref "H22") (pin "4") (pinfunction "V-_4") (pintype "power_in"))
      (node (ref "JP7") (pin "4") (pinfunction "4_4") (pintype "passive"))
      (node (ref "N11") (pin "4") (pinfunction "V-_4") (pintype "power_in"))
      (node (ref "N12") (pin "4") (pinfunction "V-_4") (pintype "power_in"))
      (node (ref "N21") (pin "4") (pinfunction "V-_4") (pintype "power_in"))
      (node (ref "N22") (pin "4") (pinfunction "V-_4") (pintype "power_in"))
      (node (ref "T11") (pin "4") (pinfunction "V-_4") (pintype "power_in"))
      (node (ref "T12") (pin "4") (pinfunction "V-_4") (pintype "power_in"))
      (node (ref "T21") (pin "4") (pinfunction "V-_4") (pintype "power_in"))
      (node (ref "T22") (pin "4") (pinfunction "V-_4") (pintype "power_in"))
    )
    (net (code "4") (name "-9V") (class "Default")
      (node (ref "C-9") (pin "-") (pinfunction "-_-") (pintype "passive"))
      (node (ref "C_INA1-") (pin "1") (pinfunction "1_1") (pintype "passive"))
      (node (ref "C_INA2-") (pin "1") (pinfunction "1_1") (pintype "passive"))
      (node (ref "INA_1") (pin "4") (pinfunction "-VS_4") (pintype "bidirectional"))
      (node (ref "INA_2") (pin "4") (pinfunction "-VS_4") (pintype "bidirectional"))
      (node (ref "JP7") (pin "1") (pinfunction "1_1") (pintype "passive"))
    )
    (net (code "5") (name "ACLK") (class "Default")
      (node (ref "CLOCK") (pin "3") (pinfunction "3_3") (pintype "passive"))
      (node (ref "U$1") (pin "35") (pinfunction "P1.2_35") (pintype "bidirectional"))
    )
    (net (code "6") (name "ACT_LED") (class "Default")
      (node (ref "LED7") (pin "C") (pinfunction "C_C") (pintype "passive"))
      (node (ref "U$1") (pin "83") (pinfunction "P6.6_83") (pintype "bidirectional"))
    )
    (net (code "7") (name "AGND") (class "Default")
      (node (ref "C+1.5") (pin "-") (pinfunction "-_-") (pintype "passive"))
      (node (ref "C+9") (pin "-") (pinfunction "-_-") (pintype "passive"))
      (node (ref "C-1.5") (pin "+") (pinfunction "+_+") (pintype "passive"))
      (node (ref "C-9") (pin "+") (pinfunction "+_+") (pintype "passive"))
      (node (ref "C22") (pin "2") (pinfunction "2_2") (pintype "passive"))
      (node (ref "C23") (pin "2") (pinfunction "2_2") (pintype "passive"))
      (node (ref "C28") (pin "2") (pinfunction "2_2") (pintype "passive"))
      (node (ref "C29") (pin "2") (pinfunction "2_2") (pintype "passive"))
      (node (ref "C30") (pin "2") (pinfunction "2_2") (pintype "passive"))
      (node (ref "C31") (pin "2") (pinfunction "2_2") (pintype "passive"))
      (node (ref "C32") (pin "2") (pinfunction "2_2") (pintype "passive"))
      (node (ref "C_H11+") (pin "2") (pinfunction "2_2") (pintype "passive"))
      (node (ref "C_H11-") (pin "1") (pinfunction "1_1") (pintype "passive"))
      (node (ref "C_H12+") (pin "2") (pinfunction "2_2") (pintype "passive"))
      (node (ref "C_H12-") (pin "1") (pinfunction "1_1") (pintype "passive"))
      (node (ref "C_H21+") (pin "2") (pinfunction "2_2") (pintype "passive"))
      (node (ref "C_H21-") (pin "1") (pinfunction "1_1") (pintype "passive"))
      (node (ref "C_H22+") (pin "2") (pinfunction "2_2") (pintype "passive"))
      (node (ref "C_H22-") (pin "1") (pinfunction "1_1") (pintype "passive"))
      (node (ref "C_INA1+") (pin "2") (pinfunction "2_2") (pintype "passive"))
      (node (ref "C_INA1-") (pin "2") (pinfunction "2_2") (pintype "passive"))
      (node (ref "C_INA2+") (pin "2") (pinfunction "2_2") (pintype "passive"))
      (node (ref "C_INA2-") (pin "2") (pinfunction "2_2") (pintype "passive"))
      (node (ref "C_N11+") (pin "2") (pinfunction "2_2") (pintype "passive"))
      (node (ref "C_N11-") (pin "1") (pinfunction "1_1") (pintype "passive"))
      (node (ref "C_N12+") (pin "2") (pinfunction "2_2") (pintype "passive"))
      (node (ref "C_N12-") (pin "1") (pinfunction "1_1") (pintype "passive"))
      (node (ref "C_N21+") (pin "2") (pinfunction "2_2") (pintype "passive"))
      (node (ref "C_N21-") (pin "1") (pinfunction "1_1") (pintype "passive"))
      (node (ref "C_N22+") (pin "2") (pinfunction "2_2") (pintype "passive"))
      (node (ref "C_N22-") (pin "1") (pinfunction "1_1") (pintype "passive"))
      (node (ref "C_T11+") (pin "2") (pinfunction "2_2") (pintype "passive"))
      (node (ref "C_T11-") (pin "1") (pinfunction "1_1") (pintype "passive"))
      (node (ref "C_T11.2") (pin "1") (pinfunction "1_1") (pintype "passive"))
      (node (ref "C_T12+") (pin "2") (pinfunction "2_2") (pintype "passive"))
      (node (ref "C_T12-") (pin "1") (pinfunction "1_1") (pintype "passive"))
      (node (ref "C_T12.2") (pin "1") (pinfunction "1_1") (pintype "passive"))
      (node (ref "C_T21+") (pin "2") (pinfunction "2_2") (pintype "passive"))
      (node (ref "C_T21-") (pin "1") (pinfunction "1_1") (pintype "passive"))
      (node (ref "C_T21.2") (pin "1") (pinfunction "1_1") (pintype "passive"))
      (node (ref "C_T22+") (pin "2") (pinfunction "2_2") (pintype "passive"))
      (node (ref "C_T22-") (pin "1") (pinfunction "1_1") (pintype "passive"))
      (node (ref "C_T22.2") (pin "1") (pinfunction "1_1") (pintype "passive"))
      (node (ref "D2") (pin "1") (pinfunction "A_1") (pintype "passive"))
      (node (ref "D3") (pin "1") (pinfunction "A_1") (pintype "passive"))
      (node (ref "JP7") (pin "2") (pinfunction "2_2") (pintype "passive"))
      (node (ref "JP7") (pin "6") (pinfunction "6_6") (pintype "passive"))
      (node (ref "R2") (pin "2") (pinfunction "2_2") (pintype "passive"))
      (node (ref "R_H11.2") (pin "1") (pinfunction "1_1") (pintype "passive"))
      (node (ref "R_H12.2") (pin "1") (pinfunction "1_1") (pintype "passive"))
      (node (ref "R_H21.2") (pin "1") (pinfunction "1_1") (pintype "passive"))
      (node (ref "R_H22.2") (pin "1") (pinfunction "1_1") (pintype "passive"))
      (node (ref "R_N1.2") (pin "1") (pinfunction "1_1") (pintype "passive"))
      (node (ref "R_N2.2") (pin "1") (pinfunction "1_1") (pintype "passive"))
      (node (ref "U$1") (pin "10") (pinfunction "AVSS2_10") (pintype "bidirectional"))
      (node (ref "U$1") (pin "12") (pinfunction "SD4P0_12") (pintype "bidirectional"))
      (node (ref "U$1") (pin "13") (pinfunction "SD4N0_13") (pintype "bidirectional"))
      (node (ref "U$1") (pin "14") (pinfunction "SD5P0_14") (pintype "bidirectional"))
      (node (ref "U$1") (pin "15") (pinfunction "SD5N0_15") (pintype "bidirectional"))
      (node (ref "U$1") (pin "16") (pinfunction "SD6P0_16") (pintype "bidirectional"))
      (node (ref "U$1") (pin "17") (pinfunction "SD6N0_17") (pintype "bidirectional"))
      (node (ref "U$1") (pin "18") (pinfunction "AVSS1_18") (pintype "bidirectional"))
      (node (ref "U$1") (pin "2") (pinfunction "SD0N0_2") (pintype "bidirectional"))
      (node (ref "U$1") (pin "3") (pinfunction "SD1P0_3") (pintype "bidirectional"))
      (node (ref "U$1") (pin "4") (pinfunction "SD1N0_4") (pintype "bidirectional"))
      (node (ref "U$1") (pin "6") (pinfunction "SD2N0_6") (pintype "bidirectional"))
      (node (ref "U$1") (pin "7") (pinfunction "SD3P0_7") (pintype "bidirectional"))
      (node (ref "U$1") (pin "8") (pinfunction "SD3N0_8") (pintype "bidirectional"))
    )
    (net (code "8") (name "AUXVCC1") (class "Default")
      (node (ref "C26") (pin "1") (pinfunction "1_1") (pintype "passive"))
      (node (ref "C27") (pin "1") (pinfunction "1_1") (pintype "passive"))
      (node (ref "U$1") (pin "22") (pinfunction "AUXVCC1_22") (pintype "bidirectional"))
    )
    (net (code "9") (name "AUXVCC2") (class "Default")
      (node (ref "C24") (pin "1") (pinfunction "1_1") (pintype "passive"))
      (node (ref "C25") (pin "1") (pinfunction "1_1") (pintype "passive"))
      (node (ref "U$1") (pin "21") (pinfunction "AUXVCC2_21") (pintype "bidirectional"))
    )
    (net (code "10") (name "AUXVCC3") (class "Default")
      (node (ref "C43") (pin "1") (pinfunction "1_1") (pintype "passive"))
      (node (ref "C44") (pin "1") (pinfunction "1_1") (pintype "passive"))
      (node (ref "U$1") (pin "29") (pinfunction "AUXVCC3_29") (pintype "bidirectional"))
    )
    (net (code "11") (name "AVCC") (class "Default")
      (node (ref "AVCC") (pin "1") (pinfunction "1_1") (pintype "passive"))
      (node (ref "C29") (pin "1") (pinfunction "1_1") (pintype "passive"))
      (node (ref "C31") (pin "1") (pinfunction "1_1") (pintype "passive"))
      (node (ref "R1") (pin "2") (pinfunction "2_2") (pintype "passive"))
      (node (ref "U$1") (pin "19") (pinfunction "AVCC_19") (pintype "bidirectional"))
    )
    (net (code "12") (name "BTN1") (class "Default")
      (node (ref "R120") (pin "2") (pinfunction "2_2") (pintype "passive"))
      (node (ref "SW1") (pin "1") (pinfunction "1_1") (pintype "passive"))
      (node (ref "U$1") (pin "87") (pinfunction "P7.2_87") (pintype "bidirectional"))
    )
    (net (code "13") (name "BTN2") (class "Default")
      (node (ref "R121") (pin "2") (pinfunction "2_2") (pintype "passive"))
      (node (ref "SW2") (pin "3") (pinfunction "3_3") (pintype "passive"))
      (node (ref "U$1") (pin "86") (pinfunction "P7.1_86") (pintype "bidirectional"))
    )
    (net (code "14") (name "BTN3") (class "Default")
      (node (ref "R122") (pin "2") (pinfunction "2_2") (pintype "passive"))
      (node (ref "SW3") (pin "1") (pinfunction "1_1") (pintype "passive"))
      (node (ref "U$1") (pin "85") (pinfunction "P7.0_85") (pintype "bidirectional"))
    )
    (net (code "15") (name "BTN4") (class "Default")
      (node (ref "R123") (pin "2") (pinfunction "2_2") (pintype "passive"))
      (node (ref "SW4") (pin "3") (pinfunction "3_3") (pintype "passive"))
      (node (ref "U$1") (pin "84") (pinfunction "P6.7_84") (pintype "bidirectional"))
    )
    (net (code "16") (name "DGND") (class "Default")
      (node (ref "C+3") (pin "-") (pinfunction "-_-") (pintype "passive"))
      (node (ref "C100") (pin "2") (pinfunction "2_2") (pintype "passive"))
      (node (ref "C101") (pin "2") (pinfunction "2_2") (pintype "passive"))
      (node (ref "C110") (pin "1") (pinfunction "1_1") (pintype "passive"))
      (node (ref "C24") (pin "2") (pinfunction "2_2") (pintype "passive"))
      (node (ref "C25") (pin "2") (pinfunction "2_2") (pintype "passive"))
      (node (ref "C26") (pin "2") (pinfunction "2_2") (pintype "passive"))
      (node (ref "C27") (pin "2") (pinfunction "2_2") (pintype "passive"))
      (node (ref "C33") (pin "2") (pinfunction "2_2") (pintype "passive"))
      (node (ref "C34") (pin "2") (pinfunction "2_2") (pintype "passive"))
      (node (ref "C35") (pin "2") (pinfunction "2_2") (pintype "passive"))
      (node (ref "C36") (pin "2") (pinfunction "2_2") (pintype "passive"))
      (node (ref "C38") (pin "2") (pinfunction "2_2") (pintype "passive"))
      (node (ref "C43") (pin "2") (pinfunction "2_2") (pintype "passive"))
      (node (ref "C44") (pin "2") (pinfunction "2_2") (pintype "passive"))
      (node (ref "CLOCK") (pin "1") (pinfunction "1_1") (pintype "passive"))
      (node (ref "DGND1") (pin "1") (pinfunction "1_1") (pintype "passive"))
      (node (ref "DGND2") (pin "1") (pinfunction "1_1") (pintype "passive"))
      (node (ref "JP7") (pin "7") (pinfunction "7_7") (pintype "passive"))
      (node (ref "JTAG") (pin "9") (pinfunction "9_9") (pintype "passive"))
      (node (ref "R2") (pin "1") (pinfunction "1_1") (pintype "passive"))
      (node (ref "SW1") (pin "4") (pinfunction "4_4") (pintype "passive"))
      (node (ref "SW2") (pin "4") (pinfunction "4_4") (pintype "passive"))
      (node (ref "SW3") (pin "4") (pinfunction "4_4") (pintype "passive"))
      (node (ref "SW4") (pin "4") (pinfunction "4_4") (pintype "passive"))
      (node (ref "SW5") (pin "4") (pinfunction "4_4") (pintype "passive"))
      (node (ref "U$1") (pin "25") (pinfunction "DVSS1_25") (pintype "bidirectional"))
      (node (ref "U$1") (pin "38") (pinfunction "COM0_38") (pintype "bidirectional"))
      (node (ref "U$1") (pin "39") (pinfunction "COM1_39") (pintype "bidirectional"))
      (node (ref "U$1") (pin "46") (pinfunction "LCDCAP_46") (pintype "bidirectional"))
      (node (ref "U$1") (pin "76") (pinfunction "DVSS2_76") (pintype "bidirectional"))
      (node (ref "XT1") (pin "P3") (pinfunction "3_P3") (pintype "bidirectional"))
    )
    (net (code "17") (name "DVCC") (class "Default")
      (node (ref "C+3") (pin "+") (pinfunction "+_+") (pintype "passive"))
      (node (ref "C33") (pin "1") (pinfunction "1_1") (pintype "passive"))
      (node (ref "C35") (pin "1") (pinfunction "1_1") (pintype "passive"))
      (node (ref "JP14") (pin "2") (pinfunction "2_2") (pintype "passive"))
      (node (ref "JP7") (pin "8") (pinfunction "8_8") (pintype "passive"))
      (node (ref "R1") (pin "1") (pinfunction "1_1") (pintype "passive"))
      (node (ref "R101") (pin "1") (pinfunction "1_1") (pintype "passive"))
      (node (ref "R110") (pin "1") (pinfunction "1_1") (pintype "passive"))
      (node (ref "R111") (pin "1") (pinfunction "1_1") (pintype "passive"))
      (node (ref "R112") (pin "1") (pinfunction "1_1") (pintype "passive"))
      (node (ref "R114") (pin "1") (pinfunction "1_1") (pintype "passive"))
      (node (ref "R115") (pin "1") (pinfunction "1_1") (pintype "passive"))
      (node (ref "R116") (pin "1") (pinfunction "1_1") (pintype "passive"))
      (node (ref "R117") (pin "1") (pinfunction "1_1") (pintype "passive"))
      (node (ref "R120") (pin "1") (pinfunction "1_1") (pintype "passive"))
      (node (ref "R121") (pin "1") (pinfunction "1_1") (pintype "passive"))
      (node (ref "R122") (pin "1") (pinfunction "1_1") (pintype "passive"))
      (node (ref "R123") (pin "1") (pinfunction "1_1") (pintype "passive"))
      (node (ref "U$1") (pin "24") (pinfunction "DVCC_24") (pintype "bidirectional"))
    )
    (net (code "18") (name "DVSYS") (class "Default")
      (node (ref "C34") (pin "1") (pinfunction "1_1") (pintype "passive"))
      (node (ref "C36") (pin "1") (pinfunction "1_1") (pintype "passive"))
      (node (ref "U$1") (pin "23") (pinfunction "VDSYS1_23") (pintype "bidirectional"))
      (node (ref "U$1") (pin "75") (pinfunction "VDSYS2_75") (pintype "bidirectional"))
    )
    (net (code "19") (name "EXT") (class "Default")
      (node (ref "JP14") (pin "3") (pinfunction "3_3") (pintype "passive"))
      (node (ref "JTAG") (pin "4") (pinfunction "4_4") (pintype "passive"))
    )
    (net (code "20") (name "H1_OUT") (class "Default")
      (node (ref "C_H12.0") (pin "1") (pinfunction "1_1") (pintype "passive"))
      (node (ref "H12") (pin "6") (pinfunction "OUT_6") (pintype "output"))
      (node (ref "JP9") (pin "2") (pinfunction "2_2") (pintype "passive"))
      (node (ref "JP9") (pin "4") (pinfunction "4_4") (pintype "passive"))
      (node (ref "JP9") (pin "6") (pinfunction "6_6") (pintype "passive"))
      (node (ref "TP2") (pin "TP") (pinfunction "TP_TP") (pintype "input"))
    )
    (net (code "21") (name "H2_OUT") (class "Default")
      (node (ref "C_H22.0") (pin "1") (pinfunction "1_1") (pintype "passive"))
      (node (ref "H22") (pin "6") (pinfunction "OUT_6") (pintype "output"))
      (node (ref "JP3") (pin "2") (pinfunction "2_2") (pintype "passive"))
      (node (ref "JP3") (pin "4") (pinfunction "4_4") (pintype "passive"))
      (node (ref "JP3") (pin "6") (pinfunction "6_6") (pintype "passive"))
      (node (ref "TP9") (pin "TP") (pinfunction "TP_TP") (pintype "input"))
    )
    (net (code "22") (name "H11_OUT") (class "Default")
      (node (ref "C_H11.0") (pin "1") (pinfunction "1_1") (pintype "passive"))
      (node (ref "C_H12.1") (pin "1") (pinfunction "1_1") (pintype "passive"))
      (node (ref "H11") (pin "6") (pinfunction "OUT_6") (pintype "output"))
      (node (ref "TP15") (pin "TP") (pinfunction "TP_TP") (pintype "input"))
    )
    (net (code "23") (name "H21_OUT") (class "Default")
      (node (ref "C_H21.0") (pin "1") (pinfunction "1_1") (pintype "passive"))
      (node (ref "C_H22.1") (pin "1") (pinfunction "1_1") (pintype "passive"))
      (node (ref "H21") (pin "6") (pinfunction "OUT_6") (pintype "output"))
      (node (ref "TP17") (pin "TP") (pinfunction "TP_TP") (pintype "input"))
    )
    (net (code "24") (name "INA1_OUT") (class "Default")
      (node (ref "INA_1") (pin "6") (pinfunction "OUT_6") (pintype "bidirectional"))
      (node (ref "JP8") (pin "2") (pinfunction "2_2") (pintype "passive"))
      (node (ref "JP8") (pin "4") (pinfunction "4_4") (pintype "passive"))
      (node (ref "JP8") (pin "6") (pinfunction "6_6") (pintype "passive"))
      (node (ref "RZ_1") (pin "2") (pinfunction "2_2") (pintype "passive"))
      (node (ref "TP1") (pin "TP") (pinfunction "TP_TP") (pintype "input"))
    )
    (net (code "25") (name "INA2_OUT") (class "Default")
      (node (ref "INA_2") (pin "6") (pinfunction "OUT_6") (pintype "bidirectional"))
      (node (ref "JP2") (pin "2") (pinfunction "2_2") (pintype "passive"))
      (node (ref "JP2") (pin "4") (pinfunction "4_4") (pintype "passive"))
      (node (ref "JP2") (pin "6") (pinfunction "6_6") (pintype "passive"))
      (node (ref "RZ_2") (pin "2") (pinfunction "2_2") (pintype "passive"))
      (node (ref "TP8") (pin "TP") (pinfunction "TP_TP") (pintype "input"))
    )
    (net (code "26") (name "INT") (class "Default")
      (node (ref "JP14") (pin "1") (pinfunction "1_1") (pintype "passive"))
      (node (ref "JTAG") (pin "2") (pinfunction "2_2") (pintype "passive"))
    )
    (net (code "27") (name "LED1") (class "Default")
      (node (ref "LED1") (pin "C") (pinfunction "C_C") (pintype "passive"))
      (node (ref "U$1") (pin "37") (pinfunction "P1.0_37") (pintype "bidirectional"))
    )
    (net (code "28") (name "LED2") (class "Default")
      (node (ref "LED2") (pin "C") (pinfunction "C_C") (pintype "passive"))
      (node (ref "U$1") (pin "36") (pinfunction "P1.1_36") (pintype "bidirectional"))
    )
    (net (code "29") (name "LED3") (class "Default")
      (node (ref "LED3") (pin "C") (pinfunction "C_C") (pintype "passive"))
      (node (ref "U$1") (pin "34") (pinfunction "P1.3_34") (pintype "bidirectional"))
    )
    (net (code "30") (name "LED4") (class "Default")
      (node (ref "LED4") (pin "C") (pinfunction "C_C") (pintype "passive"))
      (node (ref "U$1") (pin "42") (pinfunction "P2.0_42") (pintype "bidirectional"))
    )
    (net (code "31") (name "LED5") (class "Default")
      (node (ref "LED5") (pin "C") (pinfunction "C_C") (pintype "passive"))
      (node (ref "U$1") (pin "41") (pinfunction "P1.7_41") (pintype "bidirectional"))
    )
    (net (code "32") (name "LED6") (class "Default")
      (node (ref "LED6") (pin "C") (pinfunction "C_C") (pintype "passive"))
      (node (ref "U$1") (pin "40") (pinfunction "P1.6_40") (pintype "bidirectional"))
    )
    (net (code "33") (name "LS+") (class "Default")
      (node (ref "INA_2") (pin "3") (pinfunction "+IN_3") (pintype "bidirectional"))
      (node (ref "R_LS1") (pin "1") (pinfunction "1_1") (pintype "passive"))
      (node (ref "X_LS") (pin "5") (pinfunction "5_5") (pintype "bidirectional"))
    )
    (net (code "34") (name "LS-") (class "Default")
      (node (ref "INA_2") (pin "2") (pinfunction "-IN_2") (pintype "bidirectional"))
      (node (ref "R_LS1") (pin "2") (pinfunction "2_2") (pintype "passive"))
      (node (ref "X_LS") (pin "2") (pinfunction "2_2") (pintype "bidirectional"))
    )
    (net (code "35") (name "LS_TO_ADC2") (class "Default")
      (node (ref "JP16") (pin "2") (pinfunction "2_2") (pintype "passive"))
      (node (ref "JP3") (pin "5") (pinfunction "5_5") (pintype "passive"))
      (node (ref "JP4") (pin "3") (pinfunction "3_3") (pintype "passive"))
      (node (ref "JP6") (pin "1") (pinfunction "1_1") (pintype "passive"))
      (node (ref "TP6") (pin "TP") (pinfunction "TP_TP") (pintype "input"))
    )
    (net (code "36") (name "MCLK") (class "Default")
      (node (ref "CLOCK") (pin "4") (pinfunction "4_4") (pintype "passive"))
      (node (ref "U$1") (pin "33") (pinfunction "P1.4_33") (pintype "bidirectional"))
    )
    (net (code "37") (name "N1_OUT") (class "Default")
      (node (ref "C_N11.0") (pin "1") (pinfunction "1_1") (pintype "passive"))
      (node (ref "JP11") (pin "2") (pinfunction "2_2") (pintype "passive"))
      (node (ref "JP11") (pin "4") (pinfunction "4_4") (pintype "passive"))
      (node (ref "JP11") (pin "6") (pinfunction "6_6") (pintype "passive"))
      (node (ref "N11") (pin "6") (pinfunction "OUT_6") (pintype "output"))
      (node (ref "R_N1.5") (pin "2") (pinfunction "2_2") (pintype "passive"))
      (node (ref "TP4") (pin "TP") (pinfunction "TP_TP") (pintype "input"))
    )
    (net (code "38") (name "N2_OUT") (class "Default")
      (node (ref "C_N21.0") (pin "1") (pinfunction "1_1") (pintype "passive"))
      (node (ref "JP6") (pin "2") (pinfunction "2_2") (pintype "passive"))
      (node (ref "JP6") (pin "4") (pinfunction "4_4") (pintype "passive"))
      (node (ref "JP6") (pin "6") (pinfunction "6_6") (pintype "passive"))
      (node (ref "N21") (pin "6") (pinfunction "OUT_6") (pintype "output"))
      (node (ref "R_N2.5") (pin "2") (pinfunction "2_2") (pintype "passive"))
      (node (ref "TP11") (pin "TP") (pinfunction "TP_TP") (pintype "input"))
    )
    (net (code "39") (name "Net-(C_H11.1-Pad1)") (class "Default")
      (node (ref "C_H11.1") (pin "1") (pinfunction "1_1") (pintype "passive"))
      (node (ref "JP10") (pin "5") (pinfunction "5_5") (pintype "passive"))
      (node (ref "JP11") (pin "5") (pinfunction "5_5") (pintype "passive"))
      (node (ref "JP8") (pin "5") (pinfunction "5_5") (pintype "passive"))
    )
    (net (code "40") (name "Net-(C_H11.1-Pad2)") (class "Default")
      (node (ref "C_H11.1") (pin "2") (pinfunction "2_2") (pintype "passive"))
      (node (ref "C_H11.2") (pin "1") (pinfunction "1_1") (pintype "passive"))
      (node (ref "R_H11.1") (pin "1") (pinfunction "1_1") (pintype "passive"))
    )
    (net (code "41") (name "Net-(C_H12.1-Pad2)") (class "Default")
      (node (ref "C_H12.1") (pin "2") (pinfunction "2_2") (pintype "passive"))
      (node (ref "C_H12.2") (pin "1") (pinfunction "1_1") (pintype "passive"))
      (node (ref "R_H12.1") (pin "1") (pinfunction "1_1") (pintype "passive"))
    )
    (net (code "42") (name "Net-(C_H21.1-Pad1)") (class "Default")
      (node (ref "C_H21.1") (pin "1") (pinfunction "1_1") (pintype "passive"))
      (node (ref "JP2") (pin "5") (pinfunction "5_5") (pintype "passive"))
      (node (ref "JP4") (pin "5") (pinfunction "5_5") (pintype "passive"))
      (node (ref "JP6") (pin "5") (pinfunction "5_5") (pintype "passive"))
    )
    (net (code "43") (name "Net-(C_H21.1-Pad2)") (class "Default")
      (node (ref "C_H21.1") (pin "2") (pinfunction "2_2") (pintype "passive"))
      (node (ref "C_H21.2") (pin "1") (pinfunction "1_1") (pintype "passive"))
      (node (ref "R_H21.1") (pin "1") (pinfunction "1_1") (pintype "passive"))
    )
    (net (code "44") (name "Net-(C_H22.1-Pad2)") (class "Default")
      (node (ref "C_H22.1") (pin "2") (pinfunction "2_2") (pintype "passive"))
      (node (ref "C_H22.2") (pin "1") (pinfunction "1_1") (pintype "passive"))
      (node (ref "R_H22.1") (pin "1") (pinfunction "1_1") (pintype "passive"))
    )
    (net (code "45") (name "Net-(C_N1.1-Pad1)") (class "Default")
      (node (ref "C_N1.1") (pin "1") (pinfunction "1_1") (pintype "passive"))
      (node (ref "JP10") (pin "1") (pinfunction "1_1") (pintype "passive"))
      (node (ref "JP8") (pin "1") (pinfunction "1_1") (pintype "passive"))
      (node (ref "JP9") (pin "1") (pinfunction "1_1") (pintype "passive"))
      (node (ref "R_N1.1") (pin "1") (pinfunction "1_1") (pintype "passive"))
      (node (ref "R_N1.6") (pin "1") (pinfunction "1_1") (pintype "passive"))
    )
    (net (code "46") (name "Net-(C_N2.1-Pad1)") (class "Default")
      (node (ref "C_N2.1") (pin "1") (pinfunction "1_1") (pintype "passive"))
      (node (ref "JP2") (pin "1") (pinfunction "1_1") (pintype "passive"))
      (node (ref "JP3") (pin "1") (pinfunction "1_1") (pintype "passive"))
      (node (ref "JP4") (pin "1") (pinfunction "1_1") (pintype "passive"))
      (node (ref "R_N2.1") (pin "1") (pinfunction "1_1") (pintype "passive"))
      (node (ref "R_N2.6") (pin "1") (pinfunction "1_1") (pintype "passive"))
    )
    (net (code "47") (name "Net-(C_T11.1-Pad1)") (class "Default")
      (node (ref "C_T11.1") (pin "1") (pinfunction "1_1") (pintype "passive"))
      (node (ref "R_T11.1") (pin "2") (pinfunction "2_2") (pintype "passive"))
      (node (ref "R_T11.2") (pin "1") (pinfunction "1_1") (pintype "passive"))
    )
    (net (code "48") (name "Net-(C_T12.1-Pad1)") (class "Default")
      (node (ref "C_T12.1") (pin "1") (pinfunction "1_1") (pintype "passive"))
      (node (ref "R_T12.1") (pin "2") (pinfunction "2_2") (pintype "passive"))
      (node (ref "R_T12.2") (pin "1") (pinfunction "1_1") (pintype "passive"))
    )
    (net (code "49") (name "Net-(C_T21.1-Pad1)") (class "Default")
      (node (ref "C_T21.1") (pin "1") (pinfunction "1_1") (pintype "passive"))
      (node (ref "R_T21.1") (pin "2") (pinfunction "2_2") (pintype "passive"))
      (node (ref "R_T21.2") (pin "1") (pinfunction "1_1") (pintype "passive"))
    )
    (net (code "50") (name "Net-(C_T22.1-Pad1)") (class "Default")
      (node (ref "C_T22.1") (pin "1") (pinfunction "1_1") (pintype "passive"))
      (node (ref "R_T22.1") (pin "2") (pinfunction "2_2") (pintype "passive"))
      (node (ref "R_T22.2") (pin "1") (pinfunction "1_1") (pintype "passive"))
    )
    (net (code "51") (name "Net-(D1-A)") (class "Default")
      (node (ref "D1") (pin "1") (pinfunction "A_1") (pintype "passive"))
      (node (ref "RZ_1") (pin "1") (pinfunction "1_1") (pintype "passive"))
    )
    (net (code "52") (name "Net-(D1-C)") (class "Default")
      (node (ref "D1") (pin "3") (pinfunction "C_3") (pintype "passive"))
      (node (ref "D2") (pin "3") (pinfunction "C_3") (pintype "passive"))
    )
    (net (code "53") (name "Net-(D3-C)") (class "Default")
      (node (ref "D3") (pin "3") (pinfunction "C_3") (pintype "passive"))
      (node (ref "D4") (pin "3") (pinfunction "C_3") (pintype "passive"))
    )
    (net (code "54") (name "Net-(D4-A)") (class "Default")
      (node (ref "D4") (pin "1") (pinfunction "A_1") (pintype "passive"))
      (node (ref "RZ_2") (pin "1") (pinfunction "1_1") (pintype "passive"))
    )
    (net (code "55") (name "Net-(H11-IN+)") (class "Default")
      (node (ref "C_H11.2") (pin "2") (pinfunction "2_2") (pintype "passive"))
      (node (ref "H11") (pin "3") (pinfunction "IN+_3") (pintype "input"))
      (node (ref "R_H11.2") (pin "2") (pinfunction "2_2") (pintype "passive"))
    )
    (net (code "56") (name "Net-(H11-IN-)") (class "Default")
      (node (ref "C_H11.0") (pin "2") (pinfunction "2_2") (pintype "passive"))
      (node (ref "H11") (pin "2") (pinfunction "IN-_2") (pintype "input"))
      (node (ref "R_H11.1") (pin "2") (pinfunction "2_2") (pintype "passive"))
    )
    (net (code "57") (name "Net-(H12-IN+)") (class "Default")
      (node (ref "C_H12.2") (pin "2") (pinfunction "2_2") (pintype "passive"))
      (node (ref "H12") (pin "3") (pinfunction "IN+_3") (pintype "input"))
      (node (ref "R_H12.2") (pin "2") (pinfunction "2_2") (pintype "passive"))
    )
    (net (code "58") (name "Net-(H12-IN-)") (class "Default")
      (node (ref "C_H12.0") (pin "2") (pinfunction "2_2") (pintype "passive"))
      (node (ref "H12") (pin "2") (pinfunction "IN-_2") (pintype "input"))
      (node (ref "R_H12.1") (pin "2") (pinfunction "2_2") (pintype "passive"))
    )
    (net (code "59") (name "Net-(H21-IN+)") (class "Default")
      (node (ref "C_H21.2") (pin "2") (pinfunction "2_2") (pintype "passive"))
      (node (ref "H21") (pin "3") (pinfunction "IN+_3") (pintype "input"))
      (node (ref "R_H21.2") (pin "2") (pinfunction "2_2") (pintype "passive"))
    )
    (net (code "60") (name "Net-(H21-IN-)") (class "Default")
      (node (ref "C_H21.0") (pin "2") (pinfunction "2_2") (pintype "passive"))
      (node (ref "H21") (pin "2") (pinfunction "IN-_2") (pintype "input"))
      (node (ref "R_H21.1") (pin "2") (pinfunction "2_2") (pintype "passive"))
    )
    (net (code "61") (name "Net-(H22-IN+)") (class "Default")
      (node (ref "C_H22.2") (pin "2") (pinfunction "2_2") (pintype "passive"))
      (node (ref "H22") (pin "3") (pinfunction "IN+_3") (pintype "input"))
      (node (ref "R_H22.2") (pin "2") (pinfunction "2_2") (pintype "passive"))
    )
    (net (code "62") (name "Net-(H22-IN-)") (class "Default")
      (node (ref "C_H22.0") (pin "2") (pinfunction "2_2") (pintype "passive"))
      (node (ref "H22") (pin "2") (pinfunction "IN-_2") (pintype "input"))
      (node (ref "R_H22.1") (pin "2") (pinfunction "2_2") (pintype "passive"))
    )
    (net (code "63") (name "Net-(INA_1-RG-Pad1)") (class "Default")
      (node (ref "INA_1") (pin "1") (pinfunction "RG_1") (pintype "bidirectional"))
      (node (ref "JP5") (pin "1") (pinfunction "1_1") (pintype "passive"))
      (node (ref "JP5") (pin "3") (pinfunction "3_3") (pintype "passive"))
    )
    (net (code "64") (name "Net-(INA_1-RG-Pad8)") (class "Default")
      (node (ref "INA_1") (pin "8") (pinfunction "RG_8") (pintype "bidirectional"))
      (node (ref "R_INA1_CONST") (pin "2") (pinfunction "2_2") (pintype "passive"))
      (node (ref "R_INA1_MIN") (pin "2") (pinfunction "2_2") (pintype "passive"))
    )
    (net (code "65") (name "Net-(INA_2-RG-Pad1)") (class "Default")
      (node (ref "INA_2") (pin "1") (pinfunction "RG_1") (pintype "bidirectional"))
      (node (ref "JP1") (pin "1") (pinfunction "1_1") (pintype "passive"))
      (node (ref "JP1") (pin "3") (pinfunction "3_3") (pintype "passive"))
    )
    (net (code "66") (name "Net-(INA_2-RG-Pad8)") (class "Default")
      (node (ref "INA_2") (pin "8") (pinfunction "RG_8") (pintype "bidirectional"))
      (node (ref "R_INA2_CONST") (pin "2") (pinfunction "2_2") (pintype "passive"))
      (node (ref "R_INA2_MIN") (pin "2") (pinfunction "2_2") (pintype "passive"))
    )
    (net (code "67") (name "Net-(JP1-Pad4)") (class "Default")
      (node (ref "JP1") (pin "4") (pinfunction "4_4") (pintype "passive"))
      (node (ref "R_INA2_CONST") (pin "1") (pinfunction "1_1") (pintype "passive"))
    )
    (net (code "68") (name "Net-(JP2-Pad3)") (class "Default")
      (node (ref "JP2") (pin "3") (pinfunction "3_3") (pintype "passive"))
      (node (ref "JP3") (pin "3") (pinfunction "3_3") (pintype "passive"))
      (node (ref "JP6") (pin "3") (pinfunction "3_3") (pintype "passive"))
      (node (ref "R_T21.1") (pin "1") (pinfunction "1_1") (pintype "passive"))
    )
    (net (code "69") (name "Net-(JP5-Pad4)") (class "Default")
      (node (ref "JP5") (pin "4") (pinfunction "4_4") (pintype "passive"))
      (node (ref "R_INA1_CONST") (pin "1") (pinfunction "1_1") (pintype "passive"))
    )
    (net (code "70") (name "Net-(JP11-Pad3)") (class "Default")
      (node (ref "JP11") (pin "3") (pinfunction "3_3") (pintype "passive"))
      (node (ref "JP8") (pin "3") (pinfunction "3_3") (pintype "passive"))
      (node (ref "JP9") (pin "3") (pinfunction "3_3") (pintype "passive"))
      (node (ref "R_T11.1") (pin "1") (pinfunction "1_1") (pintype "passive"))
    )
    (net (code "71") (name "Net-(JP12-Pad2)") (class "Default")
      (node (ref "JP12") (pin "2") (pinfunction "2_2") (pintype "passive"))
      (node (ref "X_LS") (pin "1") (pinfunction "1_1") (pintype "bidirectional"))
    )
    (net (code "72") (name "Net-(JP13-Pad2)") (class "Default")
      (node (ref "JP13") (pin "2") (pinfunction "2_2") (pintype "passive"))
      (node (ref "X_RS") (pin "1") (pinfunction "1_1") (pintype "bidirectional"))
    )
    (net (code "73") (name "Net-(LED1-PadA)") (class "Default")
      (node (ref "LED1") (pin "A") (pinfunction "A_A") (pintype "passive"))
      (node (ref "R114") (pin "2") (pinfunction "2_2") (pintype "passive"))
    )
    (net (code "74") (name "Net-(LED2-PadA)") (class "Default")
      (node (ref "LED2") (pin "A") (pinfunction "A_A") (pintype "passive"))
      (node (ref "R115") (pin "2") (pinfunction "2_2") (pintype "passive"))
    )
    (net (code "75") (name "Net-(LED3-PadA)") (class "Default")
      (node (ref "LED3") (pin "A") (pinfunction "A_A") (pintype "passive"))
      (node (ref "R116") (pin "2") (pinfunction "2_2") (pintype "passive"))
    )
    (net (code "76") (name "Net-(LED4-PadA)") (class "Default")
      (node (ref "LED4") (pin "A") (pinfunction "A_A") (pintype "passive"))
      (node (ref "R110") (pin "2") (pinfunction "2_2") (pintype "passive"))
    )
    (net (code "77") (name "Net-(LED5-PadA)") (class "Default")
      (node (ref "LED5") (pin "A") (pinfunction "A_A") (pintype "passive"))
      (node (ref "R111") (pin "2") (pinfunction "2_2") (pintype "passive"))
    )
    (net (code "78") (name "Net-(LED6-PadA)") (class "Default")
      (node (ref "LED6") (pin "A") (pinfunction "A_A") (pintype "passive"))
      (node (ref "R112") (pin "2") (pinfunction "2_2") (pintype "passive"))
    )
    (net (code "79") (name "Net-(LED7-PadA)") (class "Default")
      (node (ref "LED7") (pin "A") (pinfunction "A_A") (pintype "passive"))
      (node (ref "R117") (pin "2") (pinfunction "2_2") (pintype "passive"))
    )
    (net (code "80") (name "Net-(N11-IN+)") (class "Default")
      (node (ref "C_N1.1") (pin "2") (pinfunction "2_2") (pintype "passive"))
      (node (ref "N11") (pin "3") (pinfunction "IN+_3") (pintype "input"))
      (node (ref "R_N1.1") (pin "2") (pinfunction "2_2") (pintype "passive"))
      (node (ref "R_N1.2") (pin "2") (pinfunction "2_2") (pintype "passive"))
      (node (ref "R_N1.3") (pin "2") (pinfunction "2_2") (pintype "passive"))
      (node (ref "R_N1.3PARALLEL") (pin "2") (pinfunction "2_2") (pintype "passive"))
    )
    (net (code "81") (name "Net-(N11-IN-)") (class "Default")
      (node (ref "C_N1.2") (pin "2") (pinfunction "2_2") (pintype "passive"))
      (node (ref "C_N11.0") (pin "2") (pinfunction "2_2") (pintype "passive"))
      (node (ref "N11") (pin "2") (pinfunction "IN-_2") (pintype "input"))
      (node (ref "R_N1.4") (pin "1") (pinfunction "1_1") (pintype "passive"))
      (node (ref "R_N1.4PARALLEL") (pin "1") (pinfunction "1_1") (pintype "passive"))
    )
    (net (code "82") (name "Net-(N12-IN+)") (class "Default")
      (node (ref "N12") (pin "3") (pinfunction "IN+_3") (pintype "input"))
      (node (ref "R_N1.5") (pin "1") (pinfunction "1_1") (pintype "passive"))
      (node (ref "R_N1.6") (pin "2") (pinfunction "2_2") (pintype "passive"))
    )
    (net (code "83") (name "Net-(N12-IN-)") (class "Default")
      (node (ref "C_N12.0") (pin "1") (pinfunction "1_1") (pintype "passive"))
      (node (ref "N12") (pin "2") (pinfunction "IN-_2") (pintype "input"))
      (node (ref "R_N1.4PARALLEL") (pin "2") (pinfunction "2_2") (pintype "passive"))
      (node (ref "R_N1.4SERIELL") (pin "2") (pinfunction "2_2") (pintype "passive"))
    )
    (net (code "84") (name "Net-(N12-OUT)") (class "Default")
      (node (ref "C_N1.2") (pin "1") (pinfunction "1_1") (pintype "passive"))
      (node (ref "C_N12.0") (pin "2") (pinfunction "2_2") (pintype "passive"))
      (node (ref "N12") (pin "6") (pinfunction "OUT_6") (pintype "output"))
      (node (ref "R_N1.3PARALLEL") (pin "1") (pinfunction "1_1") (pintype "passive"))
      (node (ref "R_N1.3SERIELL") (pin "1") (pinfunction "1_1") (pintype "passive"))
    )
    (net (code "85") (name "Net-(N21-IN+)") (class "Default")
      (node (ref "C_N2.1") (pin "2") (pinfunction "2_2") (pintype "passive"))
      (node (ref "N21") (pin "3") (pinfunction "IN+_3") (pintype "input"))
      (node (ref "R_N2.1") (pin "2") (pinfunction "2_2") (pintype "passive"))
      (node (ref "R_N2.2") (pin "2") (pinfunction "2_2") (pintype "passive"))
      (node (ref "R_N2.3") (pin "2") (pinfunction "2_2") (pintype "passive"))
      (node (ref "R_N2.3PARALLEL") (pin "2") (pinfunction "2_2") (pintype "passive"))
    )
    (net (code "86") (name "Net-(N21-IN-)") (class "Default")
      (node (ref "C_N2.2") (pin "2") (pinfunction "2_2") (pintype "passive"))
      (node (ref "C_N21.0") (pin "2") (pinfunction "2_2") (pintype "passive"))
      (node (ref "N21") (pin "2") (pinfunction "IN-_2") (pintype "input"))
      (node (ref "R_N2.4") (pin "1") (pinfunction "1_1") (pintype "passive"))
      (node (ref "R_N2.4PARALLEL") (pin "1") (pinfunction "1_1") (pintype "passive"))
    )
    (net (code "87") (name "Net-(N22-IN+)") (class "Default")
      (node (ref "N22") (pin "3") (pinfunction "IN+_3") (pintype "input"))
      (node (ref "R_N2.5") (pin "1") (pinfunction "1_1") (pintype "passive"))
      (node (ref "R_N2.6") (pin "2") (pinfunction "2_2") (pintype "passive"))
    )
    (net (code "88") (name "Net-(N22-IN-)") (class "Default")
      (node (ref "C_N22.0") (pin "1") (pinfunction "1_1") (pintype "passive"))
      (node (ref "N22") (pin "2") (pinfunction "IN-_2") (pintype "input"))
      (node (ref "R_N2.4PARALLEL") (pin "2") (pinfunction "2_2") (pintype "passive"))
      (node (ref "R_N2.4SERIAL") (pin "2") (pinfunction "2_2") (pintype "passive"))
    )
    (net (code "89") (name "Net-(N22-OUT)") (class "Default")
      (node (ref "C_N2.2") (pin "1") (pinfunction "1_1") (pintype "passive"))
      (node (ref "C_N22.0") (pin "2") (pinfunction "2_2") (pintype "passive"))
      (node (ref "N22") (pin "6") (pinfunction "OUT_6") (pintype "output"))
      (node (ref "R_N2.3PARALLEL") (pin "1") (pinfunction "1_1") (pintype "passive"))
      (node (ref "R_N2.3SERIELL") (pin "1") (pinfunction "1_1") (pintype "passive"))
    )
    (net (code "90") (name "Net-(R_INA1_VAR-A)") (class "Default")
      (node (ref "JP5") (pin "2") (pinfunction "2_2") (pintype "passive"))
      (node (ref "R_INA1_VAR") (pin "1") (pinfunction "A_1") (pintype "passive"))
    )
    (net (code "91") (name "Net-(R_INA1_VAR-S)") (class "Default")
      (node (ref "R_INA1_MIN") (pin "1") (pinfunction "1_1") (pintype "passive"))
      (node (ref "R_INA1_VAR") (pin "2") (pinfunction "S_2") (pintype "passive"))
    )
    (net (code "92") (name "Net-(R_INA2_VAR-A)") (class "Default")
      (node (ref "JP1") (pin "2") (pinfunction "2_2") (pintype "passive"))
      (node (ref "R_INA2_VAR") (pin "1") (pinfunction "A_1") (pintype "passive"))
    )
    (net (code "93") (name "Net-(R_INA2_VAR-S)") (class "Default")
      (node (ref "R_INA2_MIN") (pin "1") (pinfunction "1_1") (pintype "passive"))
      (node (ref "R_INA2_VAR") (pin "2") (pinfunction "S_2") (pintype "passive"))
    )
    (net (code "94") (name "Net-(R_N1.3-Pad1)") (class "Default")
      (node (ref "R_N1.3") (pin "1") (pinfunction "1_1") (pintype "passive"))
      (node (ref "R_N1.3SERIELL") (pin "2") (pinfunction "2_2") (pintype "passive"))
    )
    (net (code "95") (name "Net-(R_N1.4-Pad2)") (class "Default")
      (node (ref "R_N1.4") (pin "2") (pinfunction "2_2") (pintype "passive"))
      (node (ref "R_N1.4SERIELL") (pin "1") (pinfunction "1_1") (pintype "passive"))
    )
    (net (code "96") (name "Net-(R_N2.3-Pad1)") (class "Default")
      (node (ref "R_N2.3") (pin "1") (pinfunction "1_1") (pintype "passive"))
      (node (ref "R_N2.3SERIELL") (pin "2") (pinfunction "2_2") (pintype "passive"))
    )
    (net (code "97") (name "Net-(R_N2.4-Pad2)") (class "Default")
      (node (ref "R_N2.4") (pin "2") (pinfunction "2_2") (pintype "passive"))
      (node (ref "R_N2.4SERIAL") (pin "1") (pinfunction "1_1") (pintype "passive"))
    )
    (net (code "98") (name "Net-(T11-IN+)") (class "Default")
      (node (ref "C_T11.2") (pin "2") (pinfunction "2_2") (pintype "passive"))
      (node (ref "R_T11.2") (pin "2") (pinfunction "2_2") (pintype "passive"))
      (node (ref "T11") (pin "3") (pinfunction "IN+_3") (pintype "input"))
    )
    (net (code "99") (name "Net-(T11-IN-)") (class "Default")
      (node (ref "C_T11.0") (pin "2") (pinfunction "2_2") (pintype "passive"))
      (node (ref "C_T11.1") (pin "2") (pinfunction "2_2") (pintype "passive"))
      (node (ref "T11") (pin "2") (pinfunction "IN-_2") (pintype "input"))
    )
    (net (code "100") (name "Net-(T12-IN+)") (class "Default")
      (node (ref "C_T12.2") (pin "2") (pinfunction "2_2") (pintype "passive"))
      (node (ref "R_T12.2") (pin "2") (pinfunction "2_2") (pintype "passive"))
      (node (ref "T12") (pin "3") (pinfunction "IN+_3") (pintype "input"))
    )
    (net (code "101") (name "Net-(T12-IN-)") (class "Default")
      (node (ref "C_T12.0") (pin "2") (pinfunction "2_2") (pintype "passive"))
      (node (ref "C_T12.1") (pin "2") (pinfunction "2_2") (pintype "passive"))
      (node (ref "T12") (pin "2") (pinfunction "IN-_2") (pintype "input"))
    )
    (net (code "102") (name "Net-(T21-IN+)") (class "Default")
      (node (ref "C_T21.2") (pin "2") (pinfunction "2_2") (pintype "passive"))
      (node (ref "R_T21.2") (pin "2") (pinfunction "2_2") (pintype "passive"))
      (node (ref "T21") (pin "3") (pinfunction "IN+_3") (pintype "input"))
    )
    (net (code "103") (name "Net-(T21-IN-)") (class "Default")
      (node (ref "C_T21.0") (pin "2") (pinfunction "2_2") (pintype "passive"))
      (node (ref "C_T21.1") (pin "2") (pinfunction "2_2") (pintype "passive"))
      (node (ref "T21") (pin "2") (pinfunction "IN-_2") (pintype "input"))
    )
    (net (code "104") (name "Net-(T22-IN+)") (class "Default")
      (node (ref "C_T22.2") (pin "2") (pinfunction "2_2") (pintype "passive"))
      (node (ref "R_T22.2") (pin "2") (pinfunction "2_2") (pintype "passive"))
      (node (ref "T22") (pin "3") (pinfunction "IN+_3") (pintype "input"))
    )
    (net (code "105") (name "Net-(T22-IN-)") (class "Default")
      (node (ref "C_T22.0") (pin "2") (pinfunction "2_2") (pintype "passive"))
      (node (ref "C_T22.1") (pin "2") (pinfunction "2_2") (pintype "passive"))
      (node (ref "T22") (pin "2") (pinfunction "IN-_2") (pintype "input"))
    )
    (net (code "106") (name "Net-(U$1-P3.0)") (class "Default")
      (node (ref "P1") (pin "1") (pinfunction "1_1") (pintype "passive"))
      (node (ref "U$1") (pin "51") (pinfunction "P3.0_51") (pintype "bidirectional"))
    )
    (net (code "107") (name "Net-(U$1-P3.1)") (class "Default")
      (node (ref "P1") (pin "2") (pinfunction "2_2") (pintype "passive"))
      (node (ref "U$1") (pin "52") (pinfunction "P3.1_52") (pintype "bidirectional"))
    )
    (net (code "108") (name "Net-(U$1-P3.2)") (class "Default")
      (node (ref "P1") (pin "3") (pinfunction "3_3") (pintype "passive"))
      (node (ref "U$1") (pin "53") (pinfunction "P3.2_53") (pintype "bidirectional"))
    )
    (net (code "109") (name "Net-(U$1-P3.3)") (class "Default")
      (node (ref "P1") (pin "4") (pinfunction "4_4") (pintype "passive"))
      (node (ref "U$1") (pin "54") (pinfunction "P3.3_54") (pintype "bidirectional"))
    )
    (net (code "110") (name "Net-(U$1-P3.4)") (class "Default")
      (node (ref "P1") (pin "5") (pinfunction "5_5") (pintype "passive"))
      (node (ref "U$1") (pin "55") (pinfunction "P3.4_55") (pintype "bidirectional"))
    )
    (net (code "111") (name "Net-(U$1-P3.5)") (class "Default")
      (node (ref "P1") (pin "6") (pinfunction "6_6") (pintype "passive"))
      (node (ref "U$1") (pin "56") (pinfunction "P3.5_56") (pintype "bidirectional"))
    )
    (net (code "112") (name "Net-(U$1-P3.6)") (class "Default")
      (node (ref "P1") (pin "7") (pinfunction "7_7") (pintype "passive"))
      (node (ref "U$1") (pin "57") (pinfunction "P3.6_57") (pintype "bidirectional"))
    )
    (net (code "113") (name "Net-(U$1-P3.7)") (class "Default")
      (node (ref "P1") (pin "8") (pinfunction "8_8") (pintype "passive"))
      (node (ref "U$1") (pin "58") (pinfunction "P3.7_58") (pintype "bidirectional"))
    )
    (net (code "114") (name "Net-(U$1-P4.0)") (class "Default")
      (node (ref "P4") (pin "1") (pinfunction "1_1") (pintype "passive"))
      (node (ref "U$1") (pin "59") (pinfunction "P4.0_59") (pintype "bidirectional"))
    )
    (net (code "115") (name "Net-(U$1-P4.1)") (class "Default")
      (node (ref "P4") (pin "2") (pinfunction "2_2") (pintype "passive"))
      (node (ref "U$1") (pin "60") (pinfunction "P4.1_60") (pintype "bidirectional"))
    )
    (net (code "116") (name "Net-(U$1-P4.2)") (class "Default")
      (node (ref "P4") (pin "3") (pinfunction "3_3") (pintype "passive"))
      (node (ref "U$1") (pin "61") (pinfunction "P4.2_61") (pintype "bidirectional"))
    )
    (net (code "117") (name "Net-(U$1-P4.3)") (class "Default")
      (node (ref "P4") (pin "4") (pinfunction "4_4") (pintype "passive"))
      (node (ref "U$1") (pin "62") (pinfunction "P4.3_62") (pintype "bidirectional"))
    )
    (net (code "118") (name "Net-(U$1-P4.4)") (class "Default")
      (node (ref "P4") (pin "5") (pinfunction "5_5") (pintype "passive"))
      (node (ref "U$1") (pin "63") (pinfunction "P4.4_63") (pintype "bidirectional"))
    )
    (net (code "119") (name "Net-(U$1-P4.5)") (class "Default")
      (node (ref "P4") (pin "6") (pinfunction "6_6") (pintype "passive"))
      (node (ref "U$1") (pin "64") (pinfunction "P4.5_64") (pintype "bidirectional"))
    )
    (net (code "120") (name "Net-(U$1-P4.6)") (class "Default")
      (node (ref "P4") (pin "7") (pinfunction "7_7") (pintype "passive"))
      (node (ref "U$1") (pin "65") (pinfunction "P4.6_65") (pintype "bidirectional"))
    )
    (net (code "121") (name "Net-(U$1-P4.7)") (class "Default")
      (node (ref "P4") (pin "8") (pinfunction "8_8") (pintype "passive"))
      (node (ref "U$1") (pin "66") (pinfunction "P4.7_66") (pintype "bidirectional"))
    )
    (net (code "122") (name "Net-(U$1-P5.0)") (class "Default")
      (node (ref "P5") (pin "1") (pinfunction "1_1") (pintype "passive"))
      (node (ref "U$1") (pin "67") (pinfunction "P5.0_67") (pintype "bidirectional"))
    )
    (net (code "123") (name "Net-(U$1-P5.1)") (class "Default")
      (node (ref "P5") (pin "2") (pinfunction "2_2") (pintype "passive"))
      (node (ref "U$1") (pin "68") (pinfunction "P5.1_68") (pintype "bidirectional"))
    )
    (net (code "124") (name "Net-(U$1-P5.2)") (class "Default")
      (node (ref "P5") (pin "3") (pinfunction "3_3") (pintype "passive"))
      (node (ref "U$1") (pin "69") (pinfunction "P5.2_69") (pintype "bidirectional"))
    )
    (net (code "125") (name "Net-(U$1-P5.3)") (class "Default")
      (node (ref "P5") (pin "4") (pinfunction "4_4") (pintype "passive"))
      (node (ref "U$1") (pin "70") (pinfunction "P5.3_70") (pintype "bidirectional"))
    )
    (net (code "126") (name "Net-(U$1-P5.4)") (class "Default")
      (node (ref "P5") (pin "5") (pinfunction "5_5") (pintype "passive"))
      (node (ref "U$1") (pin "71") (pinfunction "P5.4_71") (pintype "bidirectional"))
    )
    (net (code "127") (name "Net-(U$1-P5.5)") (class "Default")
      (node (ref "P5") (pin "6") (pinfunction "6_6") (pintype "passive"))
      (node (ref "U$1") (pin "72") (pinfunction "P5.5_72") (pintype "bidirectional"))
    )
    (net (code "128") (name "Net-(U$1-P5.6)") (class "Default")
      (node (ref "P5") (pin "7") (pinfunction "7_7") (pintype "passive"))
      (node (ref "U$1") (pin "73") (pinfunction "P5.6_73") (pintype "bidirectional"))
    )
    (net (code "129") (name "Net-(U$1-P5.7)") (class "Default")
      (node (ref "P5") (pin "8") (pinfunction "8_8") (pintype "passive"))
      (node (ref "U$1") (pin "74") (pinfunction "P5.7_74") (pintype "bidirectional"))
    )
    (net (code "130") (name "Net-(U$1-P6.0)") (class "Default")
      (node (ref "P6") (pin "1") (pinfunction "1_1") (pintype "passive"))
      (node (ref "U$1") (pin "77") (pinfunction "P6.0_77") (pintype "bidirectional"))
    )
    (net (code "131") (name "Net-(U$1-P6.1)") (class "Default")
      (node (ref "P6") (pin "2") (pinfunction "2_2") (pintype "passive"))
      (node (ref "U$1") (pin "78") (pinfunction "P6.1_78") (pintype "bidirectional"))
    )
    (net (code "132") (name "Net-(U$1-P6.2)") (class "Default")
      (node (ref "P6") (pin "3") (pinfunction "3_3") (pintype "passive"))
      (node (ref "U$1") (pin "79") (pinfunction "P6.2_79") (pintype "bidirectional"))
    )
    (net (code "133") (name "Net-(U$1-P6.3)") (class "Default")
      (node (ref "P6") (pin "4") (pinfunction "4_4") (pintype "passive"))
      (node (ref "U$1") (pin "80") (pinfunction "P6.3_80") (pintype "bidirectional"))
    )
    (net (code "134") (name "Net-(U$1-P6.4)") (class "Default")
      (node (ref "P6") (pin "5") (pinfunction "5_5") (pintype "passive"))
      (node (ref "U$1") (pin "81") (pinfunction "P6.4_81") (pintype "bidirectional"))
    )
    (net (code "135") (name "Net-(U$1-P6.5)") (class "Default")
      (node (ref "P6") (pin "6") (pinfunction "6_6") (pintype "passive"))
      (node (ref "U$1") (pin "82") (pinfunction "P6.5_82") (pintype "bidirectional"))
    )
    (net (code "136") (name "REF") (class "Default")
      (node (ref "INA_1") (pin "5") (pinfunction "REF_5") (pintype "bidirectional"))
      (node (ref "INA_2") (pin "5") (pinfunction "REF_5") (pintype "bidirectional"))
      (node (ref "JP12") (pin "1") (pinfunction "1_1") (pintype "passive"))
      (node (ref "JP13") (pin "1") (pinfunction "1_1") (pintype "passive"))
    )
    (net (code "137") (name "RESET") (class "Default")
      (node (ref "C110") (pin "2") (pinfunction "2_2") (pintype "passive"))
      (node (ref "JTAG") (pin "11") (pinfunction "11_11") (pintype "passive"))
      (node (ref "R101") (pin "2") (pinfunction "2_2") (pintype "passive"))
      (node (ref "SW5") (pin "3") (pinfunction "3_3") (pintype "passive"))
      (node (ref "U$1") (pin "100") (pinfunction "RST/NMI/SBTDIO_100") (pintype "bidirectional"))
    )
    (net (code "138") (name "RS+") (class "Default")
      (node (ref "INA_1") (pin "3") (pinfunction "+IN_3") (pintype "bidirectional"))
      (node (ref "R_RS") (pin "1") (pinfunction "1_1") (pintype "passive"))
      (node (ref "X_RS") (pin "5") (pinfunction "5_5") (pintype "bidirectional"))
    )
    (net (code "139") (name "RS-") (class "Default")
      (node (ref "INA_1") (pin "2") (pinfunction "-IN_2") (pintype "bidirectional"))
      (node (ref "R_RS") (pin "2") (pinfunction "2_2") (pintype "passive"))
      (node (ref "X_RS") (pin "2") (pinfunction "2_2") (pintype "bidirectional"))
    )
    (net (code "140") (name "RS_TO_ADC1") (class "Default")
      (node (ref "JP10") (pin "3") (pinfunction "3_3") (pintype "passive"))
      (node (ref "JP11") (pin "1") (pinfunction "1_1") (pintype "passive"))
      (node (ref "JP15") (pin "2") (pinfunction "2_2") (pintype "passive"))
      (node (ref "JP9") (pin "5") (pinfunction "5_5") (pintype "passive"))
      (node (ref "TP5") (pin "TP") (pinfunction "TP_TP") (pintype "input"))
    )
    (net (code "141") (name "RTCCLK") (class "Default")
      (node (ref "CLOCK") (pin "2") (pinfunction "2_2") (pintype "passive"))
      (node (ref "U$1") (pin "94") (pinfunction "P8.1_94") (pintype "bidirectional"))
    )
    (net (code "142") (name "SD_IN_1P") (class "Default")
      (node (ref "JP15") (pin "1") (pinfunction "1_1") (pintype "passive"))
      (node (ref "U$1") (pin "1") (pinfunction "SD0P0_1") (pintype "bidirectional"))
    )
    (net (code "143") (name "SD_IN_2P") (class "Default")
      (node (ref "JP16") (pin "1") (pinfunction "1_1") (pintype "passive"))
      (node (ref "U$1") (pin "5") (pinfunction "SD2P0_5") (pintype "bidirectional"))
    )
    (net (code "144") (name "SMCLK") (class "Default")
      (node (ref "CLOCK") (pin "5") (pinfunction "5_5") (pintype "passive"))
      (node (ref "U$1") (pin "32") (pinfunction "P1.5_32") (pintype "bidirectional"))
    )
    (net (code "145") (name "T1_OUT") (class "Default")
      (node (ref "C_T12.0") (pin "1") (pinfunction "1_1") (pintype "passive"))
      (node (ref "JP10") (pin "2") (pinfunction "2_2") (pintype "passive"))
      (node (ref "JP10") (pin "4") (pinfunction "4_4") (pintype "passive"))
      (node (ref "JP10") (pin "6") (pinfunction "6_6") (pintype "passive"))
      (node (ref "T12") (pin "6") (pinfunction "OUT_6") (pintype "output"))
      (node (ref "TP3") (pin "TP") (pinfunction "TP_TP") (pintype "input"))
    )
    (net (code "146") (name "T2_OUT") (class "Default")
      (node (ref "C_T22.0") (pin "1") (pinfunction "1_1") (pintype "passive"))
      (node (ref "JP4") (pin "2") (pinfunction "2_2") (pintype "passive"))
      (node (ref "JP4") (pin "4") (pinfunction "4_4") (pintype "passive"))
      (node (ref "JP4") (pin "6") (pinfunction "6_6") (pintype "passive"))
      (node (ref "T22") (pin "6") (pinfunction "OUT_6") (pintype "output"))
      (node (ref "TP10") (pin "TP") (pinfunction "TP_TP") (pintype "input"))
    )
    (net (code "147") (name "T11_OUT") (class "Default")
      (node (ref "C_T11.0") (pin "1") (pinfunction "1_1") (pintype "passive"))
      (node (ref "R_T12.1") (pin "1") (pinfunction "1_1") (pintype "passive"))
      (node (ref "T11") (pin "6") (pinfunction "OUT_6") (pintype "output"))
      (node (ref "TP16") (pin "TP") (pinfunction "TP_TP") (pintype "input"))
    )
    (net (code "148") (name "T21_OUT") (class "Default")
      (node (ref "C_T21.0") (pin "1") (pinfunction "1_1") (pintype "passive"))
      (node (ref "R_T22.1") (pin "1") (pinfunction "1_1") (pintype "passive"))
      (node (ref "T21") (pin "6") (pinfunction "OUT_6") (pintype "output"))
      (node (ref "TP18") (pin "TP") (pinfunction "TP_TP") (pintype "input"))
    )
    (net (code "149") (name "TCK") (class "Default")
      (node (ref "JTAG") (pin "7") (pinfunction "7_7") (pintype "passive"))
      (node (ref "U$1") (pin "99") (pinfunction "PJ.3/TCK_99") (pintype "bidirectional"))
    )
    (net (code "150") (name "TDI") (class "Default")
      (node (ref "JTAG") (pin "3") (pinfunction "3_3") (pintype "passive"))
      (node (ref "U$1") (pin "97") (pinfunction "PJ.1/TDI/TCLK_97") (pintype "bidirectional"))
    )
    (net (code "151") (name "TDO") (class "Default")
      (node (ref "JTAG") (pin "1") (pinfunction "1_1") (pintype "passive"))
      (node (ref "U$1") (pin "96") (pinfunction "PJ.0/TDO_96") (pintype "bidirectional"))
    )
    (net (code "152") (name "TEST{slash}SBWTCK") (class "Default")
      (node (ref "JTAG") (pin "8") (pinfunction "8_8") (pintype "passive"))
      (node (ref "U$1") (pin "95") (pinfunction "TEST/SBWTCK_95") (pintype "bidirectional"))
    )
    (net (code "153") (name "TMS") (class "Default")
      (node (ref "JTAG") (pin "5") (pinfunction "5_5") (pintype "passive"))
      (node (ref "U$1") (pin "98") (pinfunction "PJ.2/TMS_98") (pintype "bidirectional"))
    )
    (net (code "154") (name "VASYS1{slash}2") (class "Default")
      (node (ref "C22") (pin "1") (pinfunction "1_1") (pintype "passive"))
      (node (ref "C23") (pin "1") (pinfunction "1_1") (pintype "passive"))
      (node (ref "C28") (pin "1") (pinfunction "1_1") (pintype "passive"))
      (node (ref "C32") (pin "1") (pinfunction "1_1") (pintype "passive"))
      (node (ref "U$1") (pin "20") (pinfunction "VASYS1_20") (pintype "bidirectional"))
      (node (ref "U$1") (pin "9") (pinfunction "VASYS2_9") (pintype "bidirectional"))
    )
    (net (code "155") (name "VCORE") (class "Default")
      (node (ref "C38") (pin "1") (pinfunction "1_1") (pintype "passive"))
      (node (ref "U$1") (pin "26") (pinfunction "VCORE_26") (pintype "bidirectional"))
    )
    (net (code "156") (name "VREF") (class "Default")
      (node (ref "C30") (pin "1") (pinfunction "1_1") (pintype "passive"))
      (node (ref "U$1") (pin "11") (pinfunction "VREF_11") (pintype "bidirectional"))
    )
    (net (code "157") (name "XIN") (class "Default")
      (node (ref "C100") (pin "1") (pinfunction "1_1") (pintype "passive"))
      (node (ref "U$1") (pin "27") (pinfunction "XIN_27") (pintype "bidirectional"))
      (node (ref "XT1") (pin "P2") (pinfunction "2_P2") (pintype "bidirectional"))
    )
    (net (code "158") (name "XOUT") (class "Default")
      (node (ref "C101") (pin "1") (pinfunction "1_1") (pintype "passive"))
      (node (ref "U$1") (pin "28") (pinfunction "XOUT_28") (pintype "bidirectional"))
      (node (ref "XT1") (pin "P1") (pinfunction "1_P1") (pintype "bidirectional"))
    )
    (net (code "159") (name "unconnected-(H11-NC1-Pad1)") (class "Default")
      (node (ref "H11") (pin "1") (pinfunction "NC1_1") (pintype "no_connect"))
    )
    (net (code "160") (name "unconnected-(H11-NC2-Pad5)") (class "Default")
      (node (ref "H11") (pin "5") (pinfunction "NC2_5") (pintype "no_connect"))
    )
    (net (code "161") (name "unconnected-(H11-NC3-Pad8)") (class "Default")
      (node (ref "H11") (pin "8") (pinfunction "NC3_8") (pintype "no_connect"))
    )
    (net (code "162") (name "unconnected-(H12-NC1-Pad1)") (class "Default")
      (node (ref "H12") (pin "1") (pinfunction "NC1_1") (pintype "no_connect"))
    )
    (net (code "163") (name "unconnected-(H12-NC2-Pad5)") (class "Default")
      (node (ref "H12") (pin "5") (pinfunction "NC2_5") (pintype "no_connect"))
    )
    (net (code "164") (name "unconnected-(H12-NC3-Pad8)") (class "Default")
      (node (ref "H12") (pin "8") (pinfunction "NC3_8") (pintype "no_connect"))
    )
    (net (code "165") (name "unconnected-(H21-NC1-Pad1)") (class "Default")
      (node (ref "H21") (pin "1") (pinfunction "NC1_1") (pintype "no_connect"))
    )
    (net (code "166") (name "unconnected-(H21-NC2-Pad5)") (class "Default")
      (node (ref "H21") (pin "5") (pinfunction "NC2_5") (pintype "no_connect"))
    )
    (net (code "167") (name "unconnected-(H21-NC3-Pad8)") (class "Default")
      (node (ref "H21") (pin "8") (pinfunction "NC3_8") (pintype "no_connect"))
    )
    (net (code "168") (name "unconnected-(H22-NC1-Pad1)") (class "Default")
      (node (ref "H22") (pin "1") (pinfunction "NC1_1") (pintype "no_connect"))
    )
    (net (code "169") (name "unconnected-(H22-NC2-Pad5)") (class "Default")
      (node (ref "H22") (pin "5") (pinfunction "NC2_5") (pintype "no_connect"))
    )
    (net (code "170") (name "unconnected-(H22-NC3-Pad8)") (class "Default")
      (node (ref "H22") (pin "8") (pinfunction "NC3_8") (pintype "no_connect"))
    )
    (net (code "171") (name "unconnected-(JTAG-Pad6)") (class "Default")
      (node (ref "JTAG") (pin "6") (pinfunction "6_6") (pintype "passive"))
    )
    (net (code "172") (name "unconnected-(JTAG-Pad10)") (class "Default")
      (node (ref "JTAG") (pin "10") (pinfunction "10_10") (pintype "passive"))
    )
    (net (code "173") (name "unconnected-(JTAG-Pad12)") (class "Default")
      (node (ref "JTAG") (pin "12") (pinfunction "12_12") (pintype "passive"))
    )
    (net (code "174") (name "unconnected-(JTAG-Pad13)") (class "Default")
      (node (ref "JTAG") (pin "13") (pinfunction "13_13") (pintype "passive"))
    )
    (net (code "175") (name "unconnected-(JTAG-Pad14)") (class "Default")
      (node (ref "JTAG") (pin "14") (pinfunction "14_14") (pintype "passive"))
    )
    (net (code "176") (name "unconnected-(N11-NC1-Pad1)") (class "Default")
      (node (ref "N11") (pin "1") (pinfunction "NC1_1") (pintype "no_connect"))
    )
    (net (code "177") (name "unconnected-(N11-NC2-Pad5)") (class "Default")
      (node (ref "N11") (pin "5") (pinfunction "NC2_5") (pintype "no_connect"))
    )
    (net (code "178") (name "unconnected-(N11-NC3-Pad8)") (class "Default")
      (node (ref "N11") (pin "8") (pinfunction "NC3_8") (pintype "no_connect"))
    )
    (net (code "179") (name "unconnected-(N12-NC1-Pad1)") (class "Default")
      (node (ref "N12") (pin "1") (pinfunction "NC1_1") (pintype "no_connect"))
    )
    (net (code "180") (name "unconnected-(N12-NC2-Pad5)") (class "Default")
      (node (ref "N12") (pin "5") (pinfunction "NC2_5") (pintype "no_connect"))
    )
    (net (code "181") (name "unconnected-(N12-NC3-Pad8)") (class "Default")
      (node (ref "N12") (pin "8") (pinfunction "NC3_8") (pintype "no_connect"))
    )
    (net (code "182") (name "unconnected-(N21-NC1-Pad1)") (class "Default")
      (node (ref "N21") (pin "1") (pinfunction "NC1_1") (pintype "no_connect"))
    )
    (net (code "183") (name "unconnected-(N21-NC2-Pad5)") (class "Default")
      (node (ref "N21") (pin "5") (pinfunction "NC2_5") (pintype "no_connect"))
    )
    (net (code "184") (name "unconnected-(N21-NC3-Pad8)") (class "Default")
      (node (ref "N21") (pin "8") (pinfunction "NC3_8") (pintype "no_connect"))
    )
    (net (code "185") (name "unconnected-(N22-NC1-Pad1)") (class "Default")
      (node (ref "N22") (pin "1") (pinfunction "NC1_1") (pintype "no_connect"))
    )
    (net (code "186") (name "unconnected-(N22-NC2-Pad5)") (class "Default")
      (node (ref "N22") (pin "5") (pinfunction "NC2_5") (pintype "no_connect"))
    )
    (net (code "187") (name "unconnected-(N22-NC3-Pad8)") (class "Default")
      (node (ref "N22") (pin "8") (pinfunction "NC3_8") (pintype "no_connect"))
    )
    (net (code "188") (name "unconnected-(R_INA1_VAR-E-Pad3)") (class "Default")
      (node (ref "R_INA1_VAR") (pin "3") (pinfunction "E_3") (pintype "passive"))
    )
    (net (code "189") (name "unconnected-(R_INA2_VAR-E-Pad3)") (class "Default")
      (node (ref "R_INA2_VAR") (pin "3") (pinfunction "E_3") (pintype "passive"))
    )
    (net (code "190") (name "unconnected-(SW1-Pad2)") (class "Default")
      (node (ref "SW1") (pin "2") (pinfunction "2_2") (pintype "passive"))
    )
    (net (code "191") (name "unconnected-(SW1-Pad3)") (class "Default")
      (node (ref "SW1") (pin "3") (pinfunction "3_3") (pintype "passive"))
    )
    (net (code "192") (name "unconnected-(SW2-Pad1)") (class "Default")
      (node (ref "SW2") (pin "1") (pinfunction "1_1") (pintype "passive"))
    )
    (net (code "193") (name "unconnected-(SW2-Pad2)") (class "Default")
      (node (ref "SW2") (pin "2") (pinfunction "2_2") (pintype "passive"))
    )
    (net (code "194") (name "unconnected-(SW3-Pad2)") (class "Default")
      (node (ref "SW3") (pin "2") (pinfunction "2_2") (pintype "passive"))
    )
    (net (code "195") (name "unconnected-(SW3-Pad3)") (class "Default")
      (node (ref "SW3") (pin "3") (pinfunction "3_3") (pintype "passive"))
    )
    (net (code "196") (name "unconnected-(SW4-Pad1)") (class "Default")
      (node (ref "SW4") (pin "1") (pinfunction "1_1") (pintype "passive"))
    )
    (net (code "197") (name "unconnected-(SW4-Pad2)") (class "Default")
      (node (ref "SW4") (pin "2") (pinfunction "2_2") (pintype "passive"))
    )
    (net (code "198") (name "unconnected-(SW5-Pad1)") (class "Default")
      (node (ref "SW5") (pin "1") (pinfunction "1_1") (pintype "passive"))
    )
    (net (code "199") (name "unconnected-(SW5-Pad2)") (class "Default")
      (node (ref "SW5") (pin "2") (pinfunction "2_2") (pintype "passive"))
    )
    (net (code "200") (name "unconnected-(T11-NC1-Pad1)") (class "Default")
      (node (ref "T11") (pin "1") (pinfunction "NC1_1") (pintype "no_connect"))
    )
    (net (code "201") (name "unconnected-(T11-NC2-Pad5)") (class "Default")
      (node (ref "T11") (pin "5") (pinfunction "NC2_5") (pintype "no_connect"))
    )
    (net (code "202") (name "unconnected-(T11-NC3-Pad8)") (class "Default")
      (node (ref "T11") (pin "8") (pinfunction "NC3_8") (pintype "no_connect"))
    )
    (net (code "203") (name "unconnected-(T12-NC1-Pad1)") (class "Default")
      (node (ref "T12") (pin "1") (pinfunction "NC1_1") (pintype "no_connect"))
    )
    (net (code "204") (name "unconnected-(T12-NC2-Pad5)") (class "Default")
      (node (ref "T12") (pin "5") (pinfunction "NC2_5") (pintype "no_connect"))
    )
    (net (code "205") (name "unconnected-(T12-NC3-Pad8)") (class "Default")
      (node (ref "T12") (pin "8") (pinfunction "NC3_8") (pintype "no_connect"))
    )
    (net (code "206") (name "unconnected-(T21-NC1-Pad1)") (class "Default")
      (node (ref "T21") (pin "1") (pinfunction "NC1_1") (pintype "no_connect"))
    )
    (net (code "207") (name "unconnected-(T21-NC2-Pad5)") (class "Default")
      (node (ref "T21") (pin "5") (pinfunction "NC2_5") (pintype "no_connect"))
    )
    (net (code "208") (name "unconnected-(T21-NC3-Pad8)") (class "Default")
      (node (ref "T21") (pin "8") (pinfunction "NC3_8") (pintype "no_connect"))
    )
    (net (code "209") (name "unconnected-(T22-NC1-Pad1)") (class "Default")
      (node (ref "T22") (pin "1") (pinfunction "NC1_1") (pintype "no_connect"))
    )
    (net (code "210") (name "unconnected-(T22-NC2-Pad5)") (class "Default")
      (node (ref "T22") (pin "5") (pinfunction "NC2_5") (pintype "no_connect"))
    )
    (net (code "211") (name "unconnected-(T22-NC3-Pad8)") (class "Default")
      (node (ref "T22") (pin "8") (pinfunction "NC3_8") (pintype "no_connect"))
    )
    (net (code "212") (name "unconnected-(U$1-P2.1-Pad43)") (class "Default")
      (node (ref "U$1") (pin "43") (pinfunction "P2.1_43") (pintype "bidirectional"))
    )
    (net (code "213") (name "unconnected-(U$1-P2.2-Pad44)") (class "Default")
      (node (ref "U$1") (pin "44") (pinfunction "P2.2_44") (pintype "bidirectional"))
    )
    (net (code "214") (name "unconnected-(U$1-P2.3-Pad45)") (class "Default")
      (node (ref "U$1") (pin "45") (pinfunction "P2.3_45") (pintype "bidirectional"))
    )
    (net (code "215") (name "unconnected-(U$1-P2.4-Pad47)") (class "Default")
      (node (ref "U$1") (pin "47") (pinfunction "P2.4_47") (pintype "bidirectional"))
    )
    (net (code "216") (name "unconnected-(U$1-P2.5-Pad48)") (class "Default")
      (node (ref "U$1") (pin "48") (pinfunction "P2.5_48") (pintype "bidirectional"))
    )
    (net (code "217") (name "unconnected-(U$1-P2.6-Pad49)") (class "Default")
      (node (ref "U$1") (pin "49") (pinfunction "P2.6_49") (pintype "bidirectional"))
    )
    (net (code "218") (name "unconnected-(U$1-P2.7-Pad50)") (class "Default")
      (node (ref "U$1") (pin "50") (pinfunction "P2.7_50") (pintype "bidirectional"))
    )
    (net (code "219") (name "unconnected-(U$1-P7.3-Pad88)") (class "Default")
      (node (ref "U$1") (pin "88") (pinfunction "P7.3_88") (pintype "bidirectional"))
    )
    (net (code "220") (name "unconnected-(U$1-P7.4-Pad89)") (class "Default")
      (node (ref "U$1") (pin "89") (pinfunction "P7.4_89") (pintype "bidirectional"))
    )
    (net (code "221") (name "unconnected-(U$1-P7.5-Pad90)") (class "Default")
      (node (ref "U$1") (pin "90") (pinfunction "P7.5_90") (pintype "bidirectional"))
    )
    (net (code "222") (name "unconnected-(U$1-P7.6-Pad91)") (class "Default")
      (node (ref "U$1") (pin "91") (pinfunction "P7.6_91") (pintype "bidirectional"))
    )
    (net (code "223") (name "unconnected-(U$1-P7.7-Pad92)") (class "Default")
      (node (ref "U$1") (pin "92") (pinfunction "P7.7_92") (pintype "bidirectional"))
    )
    (net (code "224") (name "unconnected-(U$1-P8.0-Pad93)") (class "Default")
      (node (ref "U$1") (pin "93") (pinfunction "P8.0_93") (pintype "bidirectional"))
    )
    (net (code "225") (name "unconnected-(U$1-RTCCAP0-Pad31)") (class "Default")
      (node (ref "U$1") (pin "31") (pinfunction "RTCCAP0_31") (pintype "bidirectional"))
    )
    (net (code "226") (name "unconnected-(U$1-RTCCAP1-Pad30)") (class "Default")
      (node (ref "U$1") (pin "30") (pinfunction "RTCCAP1_30") (pintype "bidirectional"))
    )
    (net (code "227") (name "unconnected-(X_LS-Pad3)") (class "Default")
      (node (ref "X_LS") (pin "3") (pinfunction "3_3") (pintype "bidirectional"))
    )
    (net (code "228") (name "unconnected-(X_LS-Pad4)") (class "Default")
      (node (ref "X_LS") (pin "4") (pinfunction "4_4") (pintype "bidirectional"))
    )
    (net (code "229") (name "unconnected-(X_RS-Pad3)") (class "Default")
      (node (ref "X_RS") (pin "3") (pinfunction "3_3") (pintype "bidirectional"))
    )
    (net (code "230") (name "unconnected-(X_RS-Pad4)") (class "Default")
      (node (ref "X_RS") (pin "4") (pinfunction "4_4") (pintype "bidirectional"))
    )
  )
)
